# stereo_mix_back_digital.net
KiCad netlist of a schematic drawn in EAGLE
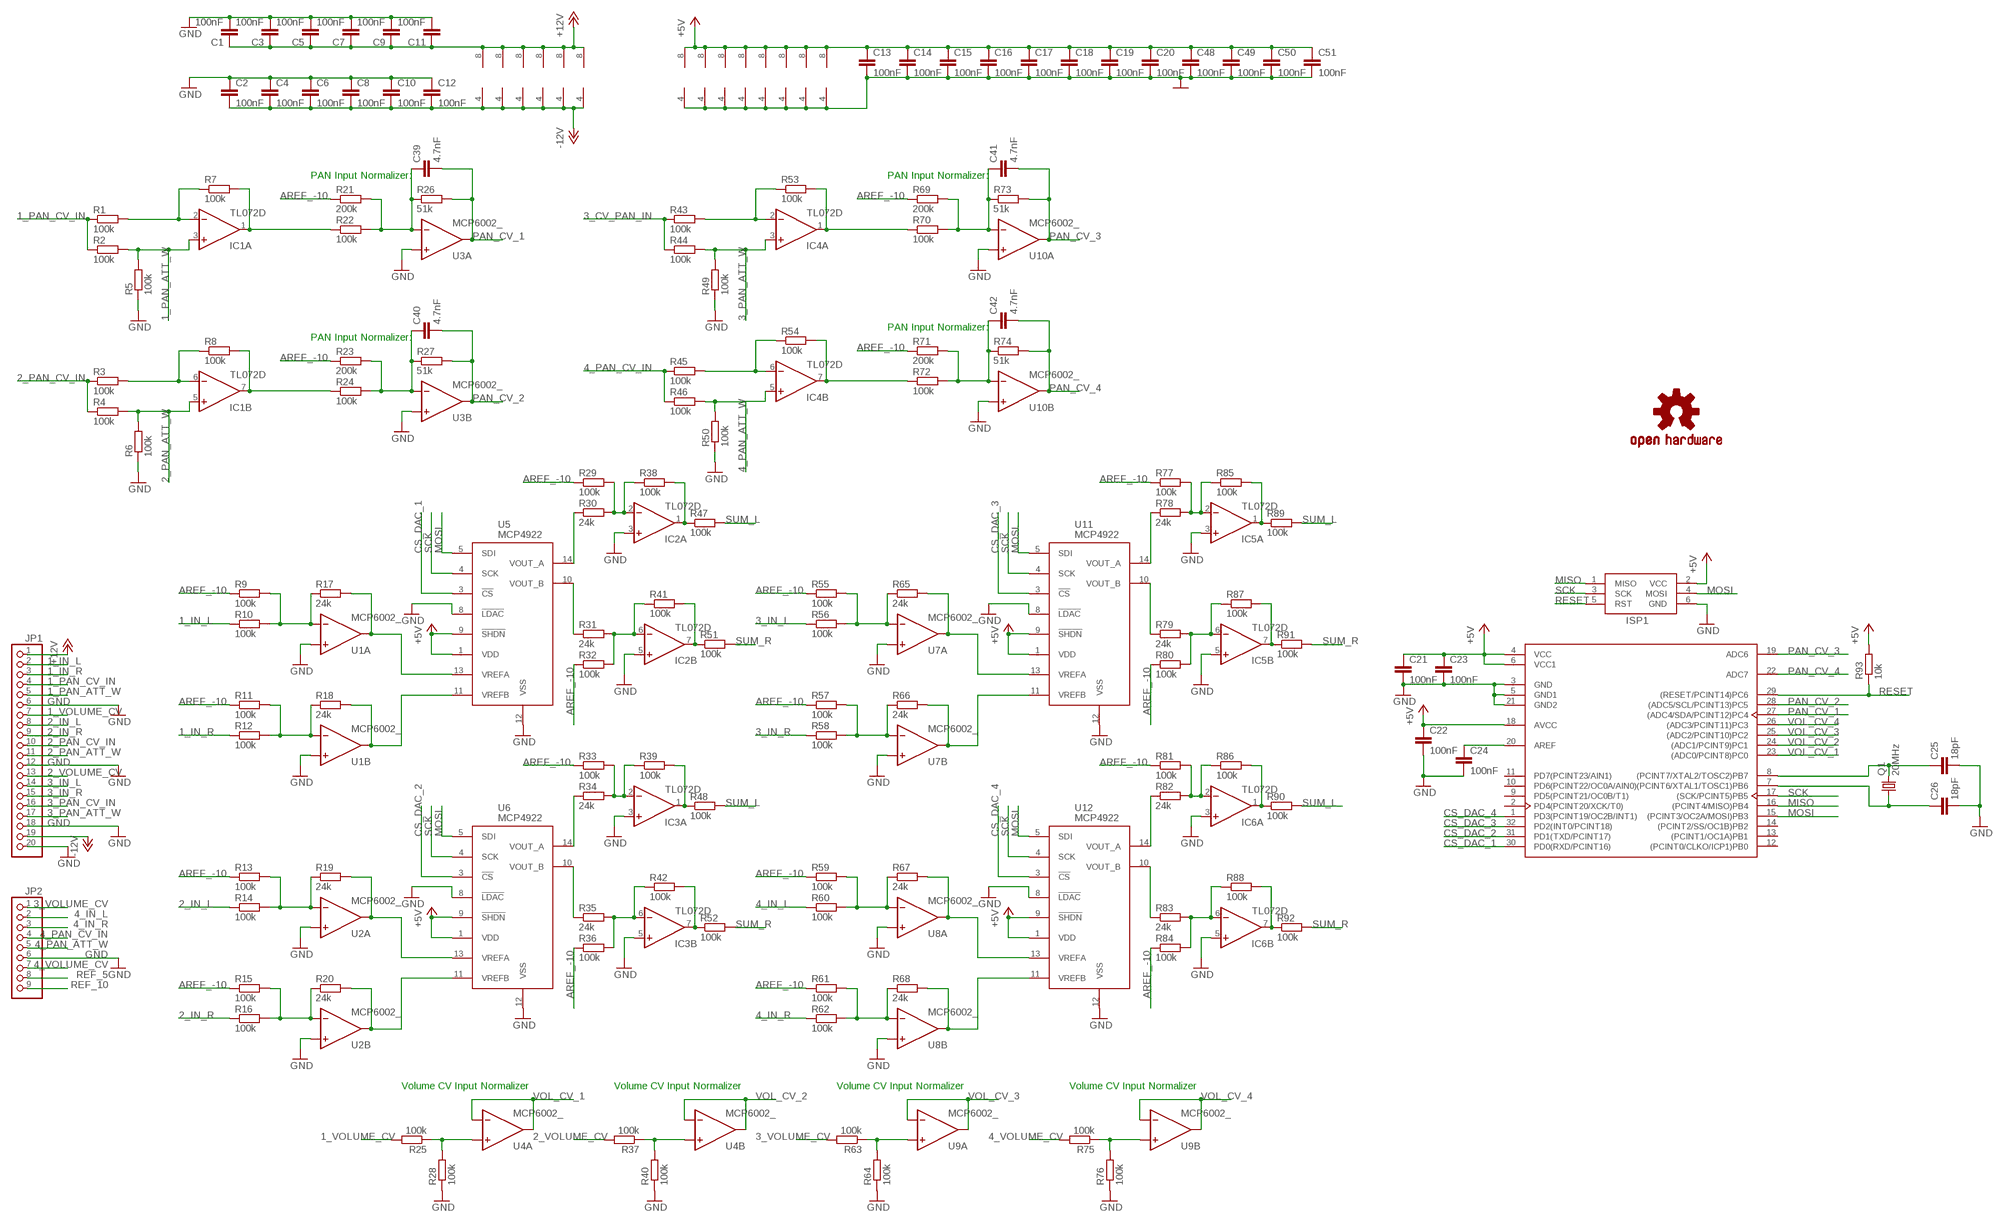
[diagram p0: schematic, sheet 1]
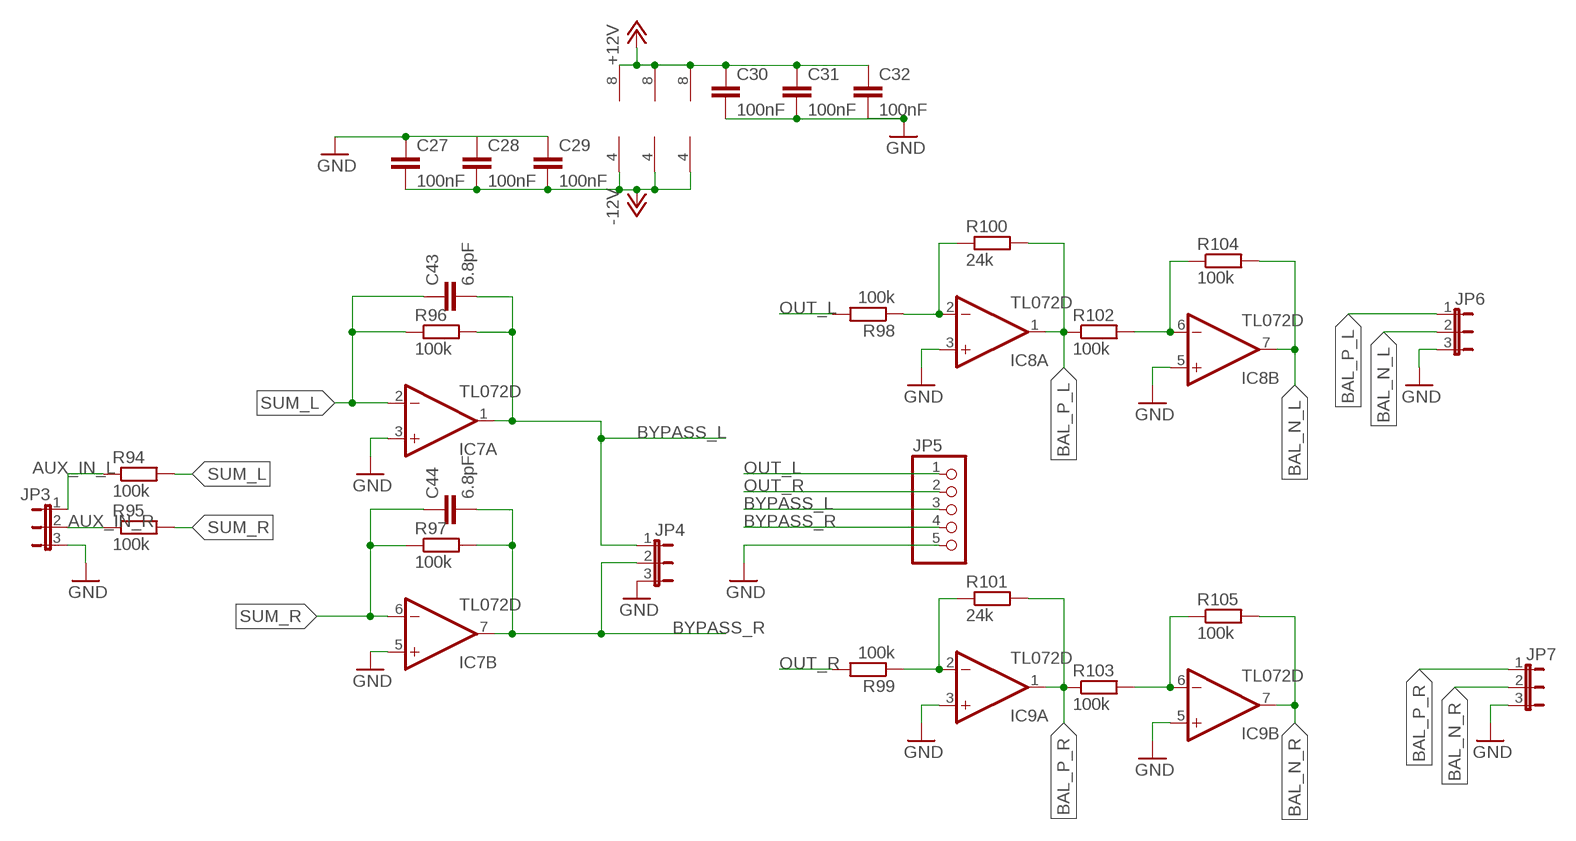
[diagram p1: schematic, sheet 2]
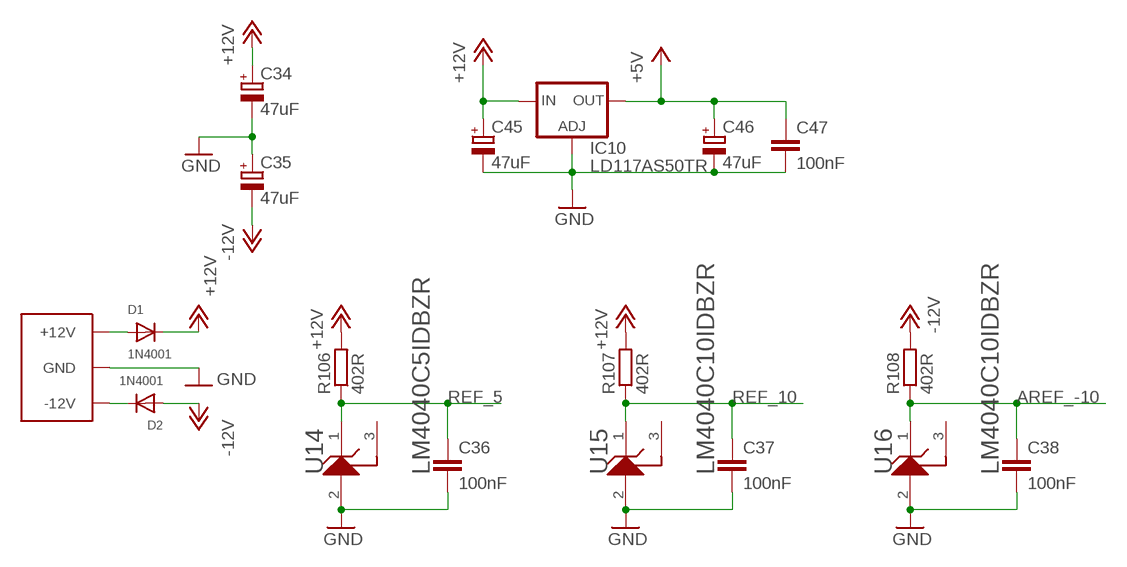
[diagram p2: schematic, sheet 3]

(export (version "E")
  (design (tool "Eeschema 10.0.6"))
  (components
    (comp (ref "C27")
      (value "100nF")
      (footprint "eagle-import:C0402")
      (libsource (lib "eagle-import") (part "resistor_348_C-EUC0402"))
    )
    (comp (ref "C28")
      (value "100nF")
      (footprint "eagle-import:C0402")
      (libsource (lib "eagle-import") (part "resistor_348_C-EUC0402"))
    )
    (comp (ref "C29")
      (value "100nF")
      (footprint "eagle-import:C0402")
      (libsource (lib "eagle-import") (part "resistor_348_C-EUC0402"))
    )
    (comp (ref "C30")
      (value "100nF")
      (footprint "eagle-import:C0402")
      (libsource (lib "eagle-import") (part "resistor_348_C-EUC0402"))
    )
    (comp (ref "C31")
      (value "100nF")
      (footprint "eagle-import:C0402")
      (libsource (lib "eagle-import") (part "resistor_348_C-EUC0402"))
    )
    (comp (ref "C32")
      (value "100nF")
      (footprint "eagle-import:C0402")
      (libsource (lib "eagle-import") (part "resistor_348_C-EUC0402"))
    )
    (comp (ref "C43")
      (value "6.8pF")
      (footprint "eagle-import:C0402")
      (libsource (lib "eagle-import") (part "resistor_348_C-EUC0402"))
    )
    (comp (ref "C44")
      (value "6.8pF")
      (footprint "eagle-import:C0402")
      (libsource (lib "eagle-import") (part "resistor_348_C-EUC0402"))
    )
    (comp (ref "IC7")
      (value "TL072D")
      (footprint "eagle-import:SO08")
      (libsource (lib "eagle-import") (part "TL072D"))
    )
    (comp (ref "IC8")
      (value "TL072D")
      (footprint "eagle-import:SO08")
      (libsource (lib "eagle-import") (part "TL072D"))
    )
    (comp (ref "IC9")
      (value "TL072D")
      (footprint "eagle-import:SO08")
      (libsource (lib "eagle-import") (part "TL072D"))
    )
    (comp (ref "JP3")
      (value "JP2E")
      (footprint "eagle-import:JP2")
      (libsource (lib "eagle-import") (part "JP2E"))
    )
    (comp (ref "JP4")
      (value "JP2E")
      (footprint "eagle-import:JP2")
      (libsource (lib "eagle-import") (part "JP2E"))
    )
    (comp (ref "JP5")
      (value "PINHD-1X5")
      (footprint "eagle-import:1X05")
      (libsource (lib "eagle-import") (part "PINHD-1X5"))
    )
    (comp (ref "JP6")
      (value "JP2E")
      (footprint "eagle-import:JP2")
      (libsource (lib "eagle-import") (part "JP2E"))
    )
    (comp (ref "JP7")
      (value "JP2E")
      (footprint "eagle-import:JP2")
      (libsource (lib "eagle-import") (part "JP2E"))
    )
    (comp (ref "R94")
      (value "100k")
      (footprint "eagle-import:R0402")
      (libsource (lib "eagle-import") (part "R-EU_R0402"))
    )
    (comp (ref "R95")
      (value "100k")
      (footprint "eagle-import:R0402")
      (libsource (lib "eagle-import") (part "R-EU_R0402"))
    )
    (comp (ref "R96")
      (value "100k")
      (footprint "eagle-import:R0402")
      (libsource (lib "eagle-import") (part "R-EU_R0402"))
    )
    (comp (ref "R97")
      (value "100k")
      (footprint "eagle-import:R0402")
      (libsource (lib "eagle-import") (part "R-EU_R0402"))
    )
    (comp (ref "R98")
      (value "100k")
      (footprint "eagle-import:R0402")
      (libsource (lib "eagle-import") (part "R-EU_R0402"))
    )
    (comp (ref "R99")
      (value "100k")
      (footprint "eagle-import:R0402")
      (libsource (lib "eagle-import") (part "R-EU_R0402"))
    )
    (comp (ref "R100")
      (value "24k")
      (footprint "eagle-import:R0402")
      (libsource (lib "eagle-import") (part "R-EU_R0402"))
    )
    (comp (ref "R101")
      (value "24k")
      (footprint "eagle-import:R0402")
      (libsource (lib "eagle-import") (part "R-EU_R0402"))
    )
    (comp (ref "R102")
      (value "100k")
      (footprint "eagle-import:R0402")
      (libsource (lib "eagle-import") (part "R-EU_R0402"))
    )
    (comp (ref "R103")
      (value "100k")
      (footprint "eagle-import:R0402")
      (libsource (lib "eagle-import") (part "R-EU_R0402"))
    )
    (comp (ref "R104")
      (value "100k")
      (footprint "eagle-import:R0402")
      (libsource (lib "eagle-import") (part "R-EU_R0402"))
    )
    (comp (ref "R105")
      (value "100k")
      (footprint "eagle-import:R0402")
      (libsource (lib "eagle-import") (part "R-EU_R0402"))
    )
    (comp (ref "C1")
      (value "100nF")
      (footprint "eagle-import:C0402")
      (libsource (lib "eagle-import") (part "resistor_348_C-EUC0402"))
    )
    (comp (ref "C2")
      (value "100nF")
      (footprint "eagle-import:C0402")
      (libsource (lib "eagle-import") (part "resistor_348_C-EUC0402"))
    )
    (comp (ref "C3")
      (value "100nF")
      (footprint "eagle-import:C0402")
      (libsource (lib "eagle-import") (part "resistor_348_C-EUC0402"))
    )
    (comp (ref "C4")
      (value "100nF")
      (footprint "eagle-import:C0402")
      (libsource (lib "eagle-import") (part "resistor_348_C-EUC0402"))
    )
    (comp (ref "C5")
      (value "100nF")
      (footprint "eagle-import:C0402")
      (libsource (lib "eagle-import") (part "resistor_348_C-EUC0402"))
    )
    (comp (ref "C6")
      (value "100nF")
      (footprint "eagle-import:C0402")
      (libsource (lib "eagle-import") (part "resistor_348_C-EUC0402"))
    )
    (comp (ref "C7")
      (value "100nF")
      (footprint "eagle-import:C0402")
      (libsource (lib "eagle-import") (part "resistor_348_C-EUC0402"))
    )
    (comp (ref "C8")
      (value "100nF")
      (footprint "eagle-import:C0402")
      (libsource (lib "eagle-import") (part "resistor_348_C-EUC0402"))
    )
    (comp (ref "C9")
      (value "100nF")
      (footprint "eagle-import:C0402")
      (libsource (lib "eagle-import") (part "resistor_348_C-EUC0402"))
    )
    (comp (ref "C10")
      (value "100nF")
      (footprint "eagle-import:C0402")
      (libsource (lib "eagle-import") (part "resistor_348_C-EUC0402"))
    )
    (comp (ref "C11")
      (value "100nF")
      (footprint "eagle-import:C0402")
      (libsource (lib "eagle-import") (part "resistor_348_C-EUC0402"))
    )
    (comp (ref "C12")
      (value "100nF")
      (footprint "eagle-import:C0402")
      (libsource (lib "eagle-import") (part "resistor_348_C-EUC0402"))
    )
    (comp (ref "C13")
      (value "100nF")
      (footprint "eagle-import:C0402")
      (libsource (lib "eagle-import") (part "resistor_348_C-EUC0402"))
    )
    (comp (ref "C14")
      (value "100nF")
      (footprint "eagle-import:C0402")
      (libsource (lib "eagle-import") (part "resistor_348_C-EUC0402"))
    )
    (comp (ref "C15")
      (value "100nF")
      (footprint "eagle-import:C0402")
      (libsource (lib "eagle-import") (part "resistor_348_C-EUC0402"))
    )
    (comp (ref "C16")
      (value "100nF")
      (footprint "eagle-import:C0402")
      (libsource (lib "eagle-import") (part "resistor_348_C-EUC0402"))
    )
    (comp (ref "C17")
      (value "100nF")
      (footprint "eagle-import:C0402")
      (libsource (lib "eagle-import") (part "resistor_348_C-EUC0402"))
    )
    (comp (ref "C18")
      (value "100nF")
      (footprint "eagle-import:C0402")
      (libsource (lib "eagle-import") (part "resistor_348_C-EUC0402"))
    )
    (comp (ref "C19")
      (value "100nF")
      (footprint "eagle-import:C0402")
      (libsource (lib "eagle-import") (part "resistor_348_C-EUC0402"))
    )
    (comp (ref "C20")
      (value "100nF")
      (footprint "eagle-import:C0402")
      (libsource (lib "eagle-import") (part "resistor_348_C-EUC0402"))
    )
    (comp (ref "C21")
      (value "100nF")
      (footprint "eagle-import:C0402")
      (libsource (lib "eagle-import") (part "resistor_348_C-EUC0402"))
    )
    (comp (ref "C22")
      (value "100nF")
      (footprint "eagle-import:C0402")
      (libsource (lib "eagle-import") (part "resistor_348_C-EUC0402"))
    )
    (comp (ref "C23")
      (value "100nF")
      (footprint "eagle-import:C0402")
      (libsource (lib "eagle-import") (part "resistor_348_C-EUC0402"))
    )
    (comp (ref "C24")
      (value "100nF")
      (footprint "eagle-import:C0402")
      (libsource (lib "eagle-import") (part "resistor_348_C-EUC0402"))
    )
    (comp (ref "C25")
      (value "18pF")
      (footprint "eagle-import:C0402")
      (libsource (lib "eagle-import") (part "resistor_348_C-EUC0402"))
    )
    (comp (ref "C26")
      (value "18pF")
      (footprint "eagle-import:C0402")
      (libsource (lib "eagle-import") (part "resistor_348_C-EUC0402"))
    )
    (comp (ref "C39")
      (value "4.7nF")
      (footprint "eagle-import:C0402")
      (libsource (lib "eagle-import") (part "resistor_348_C-EUC0402"))
    )
    (comp (ref "C40")
      (value "4.7nF")
      (footprint "eagle-import:C0402")
      (libsource (lib "eagle-import") (part "resistor_348_C-EUC0402"))
    )
    (comp (ref "C41")
      (value "4.7nF")
      (footprint "eagle-import:C0402")
      (libsource (lib "eagle-import") (part "resistor_348_C-EUC0402"))
    )
    (comp (ref "C42")
      (value "4.7nF")
      (footprint "eagle-import:C0402")
      (libsource (lib "eagle-import") (part "resistor_348_C-EUC0402"))
    )
    (comp (ref "C48")
      (value "100nF")
      (footprint "eagle-import:C0402")
      (libsource (lib "eagle-import") (part "resistor_348_C-EUC0402"))
    )
    (comp (ref "C49")
      (value "100nF")
      (footprint "eagle-import:C0402")
      (libsource (lib "eagle-import") (part "resistor_348_C-EUC0402"))
    )
    (comp (ref "C50")
      (value "100nF")
      (footprint "eagle-import:C0402")
      (libsource (lib "eagle-import") (part "resistor_348_C-EUC0402"))
    )
    (comp (ref "C51")
      (value "100nF")
      (footprint "eagle-import:C0402")
      (libsource (lib "eagle-import") (part "resistor_348_C-EUC0402"))
    )
    (comp (ref "IC1")
      (value "TL072D")
      (footprint "eagle-import:SO08")
      (libsource (lib "eagle-import") (part "TL072D"))
    )
    (comp (ref "IC2")
      (value "TL072D")
      (footprint "eagle-import:SO08")
      (libsource (lib "eagle-import") (part "TL072D"))
    )
    (comp (ref "IC3")
      (value "TL072D")
      (footprint "eagle-import:SO08")
      (libsource (lib "eagle-import") (part "TL072D"))
    )
    (comp (ref "IC4")
      (value "TL072D")
      (footprint "eagle-import:SO08")
      (libsource (lib "eagle-import") (part "TL072D"))
    )
    (comp (ref "IC5")
      (value "TL072D")
      (footprint "eagle-import:SO08")
      (libsource (lib "eagle-import") (part "TL072D"))
    )
    (comp (ref "IC6")
      (value "TL072D")
      (footprint "eagle-import:SO08")
      (libsource (lib "eagle-import") (part "TL072D"))
    )
    (comp (ref "ISP1")
      (value "AVRISP-6")
      (footprint "eagle-import:AVRISP")
      (libsource (lib "eagle-import") (part "AVRISP-6"))
    )
    (comp (ref "JP1")
      (value "PINHD-1X20")
      (footprint "eagle-import:1X20")
      (libsource (lib "eagle-import") (part "PINHD-1X20"))
    )
    (comp (ref "JP2")
      (value "PINHD-1X9")
      (footprint "eagle-import:1X09")
      (libsource (lib "eagle-import") (part "PINHD-1X9"))
    )
    (comp (ref "LOGO1")
      (value "OSHW-LOGOS")
      (footprint "eagle-import:OSHW-LOGO-S")
      (libsource (lib "eagle-import") (part "OSHW-LOGOS"))
    )
    (comp (ref "Q1")
      (value "20MHz")
      (footprint "eagle-import:HC49UP")
      (libsource (lib "eagle-import") (part "CRYSTALHC49UP"))
    )
    (comp (ref "R1")
      (value "100k")
      (footprint "eagle-import:R0402")
      (libsource (lib "eagle-import") (part "R-EU_R0402"))
    )
    (comp (ref "R2")
      (value "100k")
      (footprint "eagle-import:R0402")
      (libsource (lib "eagle-import") (part "R-EU_R0402"))
    )
    (comp (ref "R3")
      (value "100k")
      (footprint "eagle-import:R0402")
      (libsource (lib "eagle-import") (part "R-EU_R0402"))
    )
    (comp (ref "R4")
      (value "100k")
      (footprint "eagle-import:R0402")
      (libsource (lib "eagle-import") (part "R-EU_R0402"))
    )
    (comp (ref "R5")
      (value "100k")
      (footprint "eagle-import:R0402")
      (libsource (lib "eagle-import") (part "R-EU_R0402"))
    )
    (comp (ref "R6")
      (value "100k")
      (footprint "eagle-import:R0402")
      (libsource (lib "eagle-import") (part "R-EU_R0402"))
    )
    (comp (ref "R7")
      (value "100k")
      (footprint "eagle-import:R0402")
      (libsource (lib "eagle-import") (part "R-EU_R0402"))
    )
    (comp (ref "R8")
      (value "100k")
      (footprint "eagle-import:R0402")
      (libsource (lib "eagle-import") (part "R-EU_R0402"))
    )
    (comp (ref "R9")
      (value "100k")
      (footprint "eagle-import:R0402")
      (libsource (lib "eagle-import") (part "R-EU_R0402"))
    )
    (comp (ref "R10")
      (value "100k")
      (footprint "eagle-import:R0402")
      (libsource (lib "eagle-import") (part "R-EU_R0402"))
    )
    (comp (ref "R11")
      (value "100k")
      (footprint "eagle-import:R0402")
      (libsource (lib "eagle-import") (part "R-EU_R0402"))
    )
    (comp (ref "R12")
      (value "100k")
      (footprint "eagle-import:R0402")
      (libsource (lib "eagle-import") (part "R-EU_R0402"))
    )
    (comp (ref "R13")
      (value "100k")
      (footprint "eagle-import:R0402")
      (libsource (lib "eagle-import") (part "R-EU_R0402"))
    )
    (comp (ref "R14")
      (value "100k")
      (footprint "eagle-import:R0402")
      (libsource (lib "eagle-import") (part "R-EU_R0402"))
    )
    (comp (ref "R15")
      (value "100k")
      (footprint "eagle-import:R0402")
      (libsource (lib "eagle-import") (part "R-EU_R0402"))
    )
    (comp (ref "R16")
      (value "100k")
      (footprint "eagle-import:R0402")
      (libsource (lib "eagle-import") (part "R-EU_R0402"))
    )
    (comp (ref "R17")
      (value "24k")
      (footprint "eagle-import:R0402")
      (libsource (lib "eagle-import") (part "R-EU_R0402"))
    )
    (comp (ref "R18")
      (value "24k")
      (footprint "eagle-import:R0402")
      (libsource (lib "eagle-import") (part "R-EU_R0402"))
    )
    (comp (ref "R19")
      (value "24k")
      (footprint "eagle-import:R0402")
      (libsource (lib "eagle-import") (part "R-EU_R0402"))
    )
    (comp (ref "R20")
      (value "24k")
      (footprint "eagle-import:R0402")
      (libsource (lib "eagle-import") (part "R-EU_R0402"))
    )
    (comp (ref "R21")
      (value "200k")
      (footprint "eagle-import:R0402")
      (libsource (lib "eagle-import") (part "R-EU_R0402"))
    )
    (comp (ref "R22")
      (value "100k")
      (footprint "eagle-import:R0402")
      (libsource (lib "eagle-import") (part "R-EU_R0402"))
    )
    (comp (ref "R23")
      (value "200k")
      (footprint "eagle-import:R0402")
      (libsource (lib "eagle-import") (part "R-EU_R0402"))
    )
    (comp (ref "R24")
      (value "100k")
      (footprint "eagle-import:R0402")
      (libsource (lib "eagle-import") (part "R-EU_R0402"))
    )
    (comp (ref "R25")
      (value "100k")
      (footprint "eagle-import:R0402")
      (libsource (lib "eagle-import") (part "R-EU_R0402"))
    )
    (comp (ref "R26")
      (value "51k")
      (footprint "eagle-import:R0402")
      (libsource (lib "eagle-import") (part "R-EU_R0402"))
    )
    (comp (ref "R27")
      (value "51k")
      (footprint "eagle-import:R0402")
      (libsource (lib "eagle-import") (part "R-EU_R0402"))
    )
    (comp (ref "R28")
      (value "100k")
      (footprint "eagle-import:R0402")
      (libsource (lib "eagle-import") (part "R-EU_R0402"))
    )
    (comp (ref "R29")
      (value "100k")
      (footprint "eagle-import:R0402")
      (libsource (lib "eagle-import") (part "R-EU_R0402"))
    )
    (comp (ref "R30")
      (value "24k")
      (footprint "eagle-import:R0402")
      (libsource (lib "eagle-import") (part "R-EU_R0402"))
    )
    (comp (ref "R31")
      (value "24k")
      (footprint "eagle-import:R0402")
      (libsource (lib "eagle-import") (part "R-EU_R0402"))
    )
    (comp (ref "R32")
      (value "100k")
      (footprint "eagle-import:R0402")
      (libsource (lib "eagle-import") (part "R-EU_R0402"))
    )
    (comp (ref "R33")
      (value "100k")
      (footprint "eagle-import:R0402")
      (libsource (lib "eagle-import") (part "R-EU_R0402"))
    )
    (comp (ref "R34")
      (value "24k")
      (footprint "eagle-import:R0402")
      (libsource (lib "eagle-import") (part "R-EU_R0402"))
    )
    (comp (ref "R35")
      (value "24k")
      (footprint "eagle-import:R0402")
      (libsource (lib "eagle-import") (part "R-EU_R0402"))
    )
    (comp (ref "R36")
      (value "100k")
      (footprint "eagle-import:R0402")
      (libsource (lib "eagle-import") (part "R-EU_R0402"))
    )
    (comp (ref "R37")
      (value "100k")
      (footprint "eagle-import:R0402")
      (libsource (lib "eagle-import") (part "R-EU_R0402"))
    )
    (comp (ref "R38")
      (value "100k")
      (footprint "eagle-import:R0402")
      (libsource (lib "eagle-import") (part "R-EU_R0402"))
    )
    (comp (ref "R39")
      (value "100k")
      (footprint "eagle-import:R0402")
      (libsource (lib "eagle-import") (part "R-EU_R0402"))
    )
    (comp (ref "R40")
      (value "100k")
      (footprint "eagle-import:R0402")
      (libsource (lib "eagle-import") (part "R-EU_R0402"))
    )
    (comp (ref "R41")
      (value "100k")
      (footprint "eagle-import:R0402")
      (libsource (lib "eagle-import") (part "R-EU_R0402"))
    )
    (comp (ref "R42")
      (value "100k")
      (footprint "eagle-import:R0402")
      (libsource (lib "eagle-import") (part "R-EU_R0402"))
    )
    (comp (ref "R43")
      (value "100k")
      (footprint "eagle-import:R0402")
      (libsource (lib "eagle-import") (part "R-EU_R0402"))
    )
    (comp (ref "R44")
      (value "100k")
      (footprint "eagle-import:R0402")
      (libsource (lib "eagle-import") (part "R-EU_R0402"))
    )
    (comp (ref "R45")
      (value "100k")
      (footprint "eagle-import:R0402")
      (libsource (lib "eagle-import") (part "R-EU_R0402"))
    )
    (comp (ref "R46")
      (value "100k")
      (footprint "eagle-import:R0402")
      (libsource (lib "eagle-import") (part "R-EU_R0402"))
    )
    (comp (ref "R47")
      (value "100k")
      (footprint "eagle-import:R0402")
      (libsource (lib "eagle-import") (part "R-EU_R0402"))
    )
    (comp (ref "R48")
      (value "100k")
      (footprint "eagle-import:R0402")
      (libsource (lib "eagle-import") (part "R-EU_R0402"))
    )
    (comp (ref "R49")
      (value "100k")
      (footprint "eagle-import:R0402")
      (libsource (lib "eagle-import") (part "R-EU_R0402"))
    )
    (comp (ref "R50")
      (value "100k")
      (footprint "eagle-import:R0402")
      (libsource (lib "eagle-import") (part "R-EU_R0402"))
    )
    (comp (ref "R51")
      (value "100k")
      (footprint "eagle-import:R0402")
      (libsource (lib "eagle-import") (part "R-EU_R0402"))
    )
    (comp (ref "R52")
      (value "100k")
      (footprint "eagle-import:R0402")
      (libsource (lib "eagle-import") (part "R-EU_R0402"))
    )
    (comp (ref "R53")
      (value "100k")
      (footprint "eagle-import:R0402")
      (libsource (lib "eagle-import") (part "R-EU_R0402"))
    )
    (comp (ref "R54")
      (value "100k")
      (footprint "eagle-import:R0402")
      (libsource (lib "eagle-import") (part "R-EU_R0402"))
    )
    (comp (ref "R55")
      (value "100k")
      (footprint "eagle-import:R0402")
      (libsource (lib "eagle-import") (part "R-EU_R0402"))
    )
    (comp (ref "R56")
      (value "100k")
      (footprint "eagle-import:R0402")
      (libsource (lib "eagle-import") (part "R-EU_R0402"))
    )
    (comp (ref "R57")
      (value "100k")
      (footprint "eagle-import:R0402")
      (libsource (lib "eagle-import") (part "R-EU_R0402"))
    )
    (comp (ref "R58")
      (value "100k")
      (footprint "eagle-import:R0402")
      (libsource (lib "eagle-import") (part "R-EU_R0402"))
    )
    (comp (ref "R59")
      (value "100k")
      (footprint "eagle-import:R0402")
      (libsource (lib "eagle-import") (part "R-EU_R0402"))
    )
    (comp (ref "R60")
      (value "100k")
      (footprint "eagle-import:R0402")
      (libsource (lib "eagle-import") (part "R-EU_R0402"))
    )
    (comp (ref "R61")
      (value "100k")
      (footprint "eagle-import:R0402")
      (libsource (lib "eagle-import") (part "R-EU_R0402"))
    )
    (comp (ref "R62")
      (value "100k")
      (footprint "eagle-import:R0402")
      (libsource (lib "eagle-import") (part "R-EU_R0402"))
    )
    (comp (ref "R63")
      (value "100k")
      (footprint "eagle-import:R0402")
      (libsource (lib "eagle-import") (part "R-EU_R0402"))
    )
    (comp (ref "R64")
      (value "100k")
      (footprint "eagle-import:R0402")
      (libsource (lib "eagle-import") (part "R-EU_R0402"))
    )
    (comp (ref "R65")
      (value "24k")
      (footprint "eagle-import:R0402")
      (libsource (lib "eagle-import") (part "R-EU_R0402"))
    )
    (comp (ref "R66")
      (value "24k")
      (footprint "eagle-import:R0402")
      (libsource (lib "eagle-import") (part "R-EU_R0402"))
    )
    (comp (ref "R67")
      (value "24k")
      (footprint "eagle-import:R0402")
      (libsource (lib "eagle-import") (part "R-EU_R0402"))
    )
    (comp (ref "R68")
      (value "24k")
      (footprint "eagle-import:R0402")
      (libsource (lib "eagle-import") (part "R-EU_R0402"))
    )
    (comp (ref "R69")
      (value "200k")
      (footprint "eagle-import:R0402")
      (libsource (lib "eagle-import") (part "R-EU_R0402"))
    )
    (comp (ref "R70")
      (value "100k")
      (footprint "eagle-import:R0402")
      (libsource (lib "eagle-import") (part "R-EU_R0402"))
    )
    (comp (ref "R71")
      (value "200k")
      (footprint "eagle-import:R0402")
      (libsource (lib "eagle-import") (part "R-EU_R0402"))
    )
    (comp (ref "R72")
      (value "100k")
      (footprint "eagle-import:R0402")
      (libsource (lib "eagle-import") (part "R-EU_R0402"))
    )
    (comp (ref "R73")
      (value "51k")
      (footprint "eagle-import:R0402")
      (libsource (lib "eagle-import") (part "R-EU_R0402"))
    )
    (comp (ref "R74")
      (value "51k")
      (footprint "eagle-import:R0402")
      (libsource (lib "eagle-import") (part "R-EU_R0402"))
    )
    (comp (ref "R75")
      (value "100k")
      (footprint "eagle-import:R0402")
      (libsource (lib "eagle-import") (part "R-EU_R0402"))
    )
    (comp (ref "R76")
      (value "100k")
      (footprint "eagle-import:R0402")
      (libsource (lib "eagle-import") (part "R-EU_R0402"))
    )
    (comp (ref "R77")
      (value "100k")
      (footprint "eagle-import:R0402")
      (libsource (lib "eagle-import") (part "R-EU_R0402"))
    )
    (comp (ref "R78")
      (value "24k")
      (footprint "eagle-import:R0402")
      (libsource (lib "eagle-import") (part "R-EU_R0402"))
    )
    (comp (ref "R79")
      (value "24k")
      (footprint "eagle-import:R0402")
      (libsource (lib "eagle-import") (part "R-EU_R0402"))
    )
    (comp (ref "R80")
      (value "100k")
      (footprint "eagle-import:R0402")
      (libsource (lib "eagle-import") (part "R-EU_R0402"))
    )
    (comp (ref "R81")
      (value "100k")
      (footprint "eagle-import:R0402")
      (libsource (lib "eagle-import") (part "R-EU_R0402"))
    )
    (comp (ref "R82")
      (value "24k")
      (footprint "eagle-import:R0402")
      (libsource (lib "eagle-import") (part "R-EU_R0402"))
    )
    (comp (ref "R83")
      (value "24k")
      (footprint "eagle-import:R0402")
      (libsource (lib "eagle-import") (part "R-EU_R0402"))
    )
    (comp (ref "R84")
      (value "100k")
      (footprint "eagle-import:R0402")
      (libsource (lib "eagle-import") (part "R-EU_R0402"))
    )
    (comp (ref "R85")
      (value "100k")
      (footprint "eagle-import:R0402")
      (libsource (lib "eagle-import") (part "R-EU_R0402"))
    )
    (comp (ref "R86")
      (value "100k")
      (footprint "eagle-import:R0402")
      (libsource (lib "eagle-import") (part "R-EU_R0402"))
    )
    (comp (ref "R87")
      (value "100k")
      (footprint "eagle-import:R0402")
      (libsource (lib "eagle-import") (part "R-EU_R0402"))
    )
    (comp (ref "R88")
      (value "100k")
      (footprint "eagle-import:R0402")
      (libsource (lib "eagle-import") (part "R-EU_R0402"))
    )
    (comp (ref "R89")
      (value "100k")
      (footprint "eagle-import:R0402")
      (libsource (lib "eagle-import") (part "R-EU_R0402"))
    )
    (comp (ref "R90")
      (value "100k")
      (footprint "eagle-import:R0402")
      (libsource (lib "eagle-import") (part "R-EU_R0402"))
    )
    (comp (ref "R91")
      (value "100k")
      (footprint "eagle-import:R0402")
      (libsource (lib "eagle-import") (part "R-EU_R0402"))
    )
    (comp (ref "R92")
      (value "100k")
      (footprint "eagle-import:R0402")
      (libsource (lib "eagle-import") (part "R-EU_R0402"))
    )
    (comp (ref "R93")
      (value "10k")
      (footprint "eagle-import:R0402")
      (libsource (lib "eagle-import") (part "R-EU_R0402"))
    )
    (comp (ref "U1")
      (value "MCP6002_")
      (footprint "eagle-import:SO08")
      (libsource (lib "eagle-import") (part "MCP6002_"))
    )
    (comp (ref "U2")
      (value "MCP6002_")
      (footprint "eagle-import:SO08")
      (libsource (lib "eagle-import") (part "MCP6002_"))
    )
    (comp (ref "U3")
      (value "MCP6002_")
      (footprint "eagle-import:SO08")
      (libsource (lib "eagle-import") (part "MCP6002_"))
    )
    (comp (ref "U4")
      (value "MCP6002_")
      (footprint "eagle-import:SO08")
      (libsource (lib "eagle-import") (part "MCP6002_"))
    )
    (comp (ref "U5")
      (value "MCP4922")
      (footprint "eagle-import:SO-14")
      (libsource (lib "eagle-import") (part "MCP4922"))
    )
    (comp (ref "U6")
      (value "MCP4922")
      (footprint "eagle-import:SO-14")
      (libsource (lib "eagle-import") (part "MCP4922"))
    )
    (comp (ref "U7")
      (value "MCP6002_")
      (footprint "eagle-import:SO08")
      (libsource (lib "eagle-import") (part "MCP6002_"))
    )
    (comp (ref "U8")
      (value "MCP6002_")
      (footprint "eagle-import:SO08")
      (libsource (lib "eagle-import") (part "MCP6002_"))
    )
    (comp (ref "U9")
      (value "MCP6002_")
      (footprint "eagle-import:SO08")
      (libsource (lib "eagle-import") (part "MCP6002_"))
    )
    (comp (ref "U10")
      (value "MCP6002_")
      (footprint "eagle-import:SO08")
      (libsource (lib "eagle-import") (part "MCP6002_"))
    )
    (comp (ref "U11")
      (value "MCP4922")
      (footprint "eagle-import:SO-14")
      (libsource (lib "eagle-import") (part "MCP4922"))
    )
    (comp (ref "U12")
      (value "MCP4922")
      (footprint "eagle-import:SO-14")
      (libsource (lib "eagle-import") (part "MCP4922"))
    )
    (comp (ref "U13")
      (value "ATMEGA328P-AU")
      (footprint "eagle-import:TQFP-32")
      (fields
        (field (name "DIGIKEY_PART_NUMBER") "ATMEGA328P-AU-ND")
        (field (name "MANUFACTURER") "Microchip Technology")
        (field (name "CREATED_BY") "PCBLayout.com")
      )
      (libsource (lib "eagle-import") (part "ATMEGA328P-AU"))
    )
    (comp (ref "C33")
      (value "EURO_POWER_LOCKFAT-LOCK")
      (footprint "eagle-import:EURO_PWR_HEADER_LOCK")
      (libsource (lib "eagle-import") (part "EURO_POWER_LOCKFAT-LOCK"))
    )
    (comp (ref "C34")
      (value "47uF")
      (footprint "eagle-import:PANASONIC_C")
      (libsource (lib "eagle-import") (part "CPOL-EUC"))
    )
    (comp (ref "C35")
      (value "47uF")
      (footprint "eagle-import:PANASONIC_C")
      (libsource (lib "eagle-import") (part "CPOL-EUC"))
    )
    (comp (ref "C36")
      (value "100nF")
      (footprint "eagle-import:C0402")
      (libsource (lib "eagle-import") (part "resistor_348_C-EUC0402"))
    )
    (comp (ref "C37")
      (value "100nF")
      (footprint "eagle-import:C0402")
      (libsource (lib "eagle-import") (part "resistor_348_C-EUC0402"))
    )
    (comp (ref "C38")
      (value "100nF")
      (footprint "eagle-import:C0402")
      (libsource (lib "eagle-import") (part "resistor_348_C-EUC0402"))
    )
    (comp (ref "C45")
      (value "47uF")
      (footprint "eagle-import:PANASONIC_C")
      (libsource (lib "eagle-import") (part "CPOL-EUC"))
    )
    (comp (ref "C46")
      (value "47uF")
      (footprint "eagle-import:PANASONIC_C")
      (libsource (lib "eagle-import") (part "CPOL-EUC"))
    )
    (comp (ref "C47")
      (value "100nF")
      (footprint "eagle-import:C0402")
      (libsource (lib "eagle-import") (part "resistor_348_C-EUC0402"))
    )
    (comp (ref "D1")
      (value "1N4001")
      (footprint "eagle-import:SMADIODE")
      (libsource (lib "eagle-import") (part "DIODESMA"))
    )
    (comp (ref "D2")
      (value "1N4001")
      (footprint "eagle-import:SMADIODE")
      (libsource (lib "eagle-import") (part "DIODESMA"))
    )
    (comp (ref "IC10")
      (value "LD117AS50TR")
      (footprint "eagle-import:SOT223")
      (libsource (lib "eagle-import") (part "LD117A?S50TR"))
    )
    (comp (ref "R106")
      (value "402R")
      (footprint "eagle-import:R0402")
      (libsource (lib "eagle-import") (part "R-EU_R0402"))
    )
    (comp (ref "R107")
      (value "402R")
      (footprint "eagle-import:R0402")
      (libsource (lib "eagle-import") (part "R-EU_R0402"))
    )
    (comp (ref "R108")
      (value "402R")
      (footprint "eagle-import:R0402")
      (libsource (lib "eagle-import") (part "R-EU_R0402"))
    )
    (comp (ref "U14")
      (value "TEXAS_INSTRUMENTS_LM4040C5IDBZR")
      (footprint "eagle-import:TEXAS_INSTRUMENTS_LM4040C5IDBZR_0")
      (libsource (lib "eagle-import") (part "TEXAS_INSTRUMENTS_LM4040C5IDBZR"))
    )
    (comp (ref "U15")
      (value "TEXAS_INSTRUMENTS_LM4040C10IDBZR")
      (footprint "eagle-import:TEXAS_INSTRUMENTS_LM4040C5IDBZR_0")
      (libsource (lib "eagle-import") (part "TEXAS_INSTRUMENTS_LM4040C10IDBZR"))
    )
    (comp (ref "U16")
      (value "TEXAS_INSTRUMENTS_LM4040C10IDBZR")
      (footprint "eagle-import:TEXAS_INSTRUMENTS_LM4040C5IDBZR_0")
      (libsource (lib "eagle-import") (part "TEXAS_INSTRUMENTS_LM4040C10IDBZR"))
    )
  )
  (nets
    (net (code "1") (name "+5V") (class "Default")
      (node (ref "C13") (pin "1") (pinfunction "1_1") (pintype "passive"))
      (node (ref "C14") (pin "1") (pinfunction "1_1") (pintype "passive"))
      (node (ref "C15") (pin "1") (pinfunction "1_1") (pintype "passive"))
      (node (ref "C16") (pin "1") (pinfunction "1_1") (pintype "passive"))
      (node (ref "C17") (pin "1") (pinfunction "1_1") (pintype "passive"))
      (node (ref "C18") (pin "1") (pinfunction "1_1") (pintype "passive"))
      (node (ref "C19") (pin "1") (pinfunction "1_1") (pintype "passive"))
      (node (ref "C20") (pin "1") (pinfunction "1_1") (pintype "passive"))
      (node (ref "C21") (pin "1") (pinfunction "1_1") (pintype "passive"))
      (node (ref "C22") (pin "1") (pinfunction "1_1") (pintype "passive"))
      (node (ref "C23") (pin "1") (pinfunction "1_1") (pintype "passive"))
      (node (ref "C46") (pin "+") (pinfunction "+_+") (pintype "passive"))
      (node (ref "C47") (pin "1") (pinfunction "1_1") (pintype "passive"))
      (node (ref "C48") (pin "1") (pinfunction "1_1") (pintype "passive"))
      (node (ref "C49") (pin "1") (pinfunction "1_1") (pintype "passive"))
      (node (ref "C50") (pin "1") (pinfunction "1_1") (pintype "passive"))
      (node (ref "C51") (pin "1") (pinfunction "1_1") (pintype "passive"))
      (node (ref "IC10") (pin "4") (pinfunction "OUT_4") (pintype "passive"))
      (node (ref "ISP1") (pin "2") (pinfunction "VCC_2") (pintype "power_in"))
      (node (ref "R93") (pin "2") (pinfunction "2_2") (pintype "passive"))
      (node (ref "U1") (pin "8") (pinfunction "V+_8") (pintype "power_in"))
      (node (ref "U10") (pin "8") (pinfunction "V+_8") (pintype "power_in"))
      (node (ref "U11") (pin "1") (pinfunction "VDD_1") (pintype "bidirectional"))
      (node (ref "U11") (pin "9") (pinfunction "~{SHDN}_9") (pintype "bidirectional"))
      (node (ref "U12") (pin "1") (pinfunction "VDD_1") (pintype "bidirectional"))
      (node (ref "U12") (pin "9") (pinfunction "~{SHDN}_9") (pintype "bidirectional"))
      (node (ref "U13") (pin "18") (pinfunction "AVCC_18") (pintype "power_in"))
      (node (ref "U13") (pin "4") (pinfunction "VCC_4") (pintype "power_in"))
      (node (ref "U13") (pin "6") (pinfunction "VCC1_6") (pintype "power_in"))
      (node (ref "U2") (pin "8") (pinfunction "V+_8") (pintype "power_in"))
      (node (ref "U3") (pin "8") (pinfunction "V+_8") (pintype "power_in"))
      (node (ref "U4") (pin "8") (pinfunction "V+_8") (pintype "power_in"))
      (node (ref "U5") (pin "1") (pinfunction "VDD_1") (pintype "bidirectional"))
      (node (ref "U5") (pin "9") (pinfunction "~{SHDN}_9") (pintype "bidirectional"))
      (node (ref "U6") (pin "1") (pinfunction "VDD_1") (pintype "bidirectional"))
      (node (ref "U6") (pin "9") (pinfunction "~{SHDN}_9") (pintype "bidirectional"))
      (node (ref "U7") (pin "8") (pinfunction "V+_8") (pintype "power_in"))
      (node (ref "U8") (pin "8") (pinfunction "V+_8") (pintype "power_in"))
      (node (ref "U9") (pin "8") (pinfunction "V+_8") (pintype "power_in"))
    )
    (net (code "2") (name "+12V") (class "Default")
      (node (ref "C1") (pin "1") (pinfunction "1_1") (pintype "passive"))
      (node (ref "C11") (pin "1") (pinfunction "1_1") (pintype "passive"))
      (node (ref "C3") (pin "1") (pinfunction "1_1") (pintype "passive"))
      (node (ref "C30") (pin "1") (pinfunction "1_1") (pintype "passive"))
      (node (ref "C31") (pin "1") (pinfunction "1_1") (pintype "passive"))
      (node (ref "C32") (pin "1") (pinfunction "1_1") (pintype "passive"))
      (node (ref "C34") (pin "+") (pinfunction "+_+") (pintype "passive"))
      (node (ref "C45") (pin "+") (pinfunction "+_+") (pintype "passive"))
      (node (ref "C5") (pin "1") (pinfunction "1_1") (pintype "passive"))
      (node (ref "C7") (pin "1") (pinfunction "1_1") (pintype "passive"))
      (node (ref "C9") (pin "1") (pinfunction "1_1") (pintype "passive"))
      (node (ref "D1") (pin "C") (pinfunction "C_C") (pintype "passive"))
      (node (ref "IC1") (pin "8") (pinfunction "V+_8") (pintype "power_in"))
      (node (ref "IC10") (pin "3") (pinfunction "IN_3") (pintype "input"))
      (node (ref "IC2") (pin "8") (pinfunction "V+_8") (pintype "power_in"))
      (node (ref "IC3") (pin "8") (pinfunction "V+_8") (pintype "power_in"))
      (node (ref "IC4") (pin "8") (pinfunction "V+_8") (pintype "power_in"))
      (node (ref "IC5") (pin "8") (pinfunction "V+_8") (pintype "power_in"))
      (node (ref "IC6") (pin "8") (pinfunction "V+_8") (pintype "power_in"))
      (node (ref "IC7") (pin "8") (pinfunction "V+_8") (pintype "power_in"))
      (node (ref "IC8") (pin "8") (pinfunction "V+_8") (pintype "power_in"))
      (node (ref "IC9") (pin "8") (pinfunction "V+_8") (pintype "power_in"))
      (node (ref "JP1") (pin "1") (pinfunction "1_1") (pintype "passive"))
      (node (ref "R106") (pin "2") (pinfunction "2_2") (pintype "passive"))
      (node (ref "R107") (pin "2") (pinfunction "2_2") (pintype "passive"))
    )
    (net (code "3") (name "-12V") (class "Default")
      (node (ref "C10") (pin "2") (pinfunction "2_2") (pintype "passive"))
      (node (ref "C12") (pin "2") (pinfunction "2_2") (pintype "passive"))
      (node (ref "C2") (pin "2") (pinfunction "2_2") (pintype "passive"))
      (node (ref "C27") (pin "2") (pinfunction "2_2") (pintype "passive"))
      (node (ref "C28") (pin "2") (pinfunction "2_2") (pintype "passive"))
      (node (ref "C29") (pin "2") (pinfunction "2_2") (pintype "passive"))
      (node (ref "C35") (pin "-") (pinfunction "-_-") (pintype "passive"))
      (node (ref "C4") (pin "2") (pinfunction "2_2") (pintype "passive"))
      (node (ref "C6") (pin "2") (pinfunction "2_2") (pintype "passive"))
      (node (ref "C8") (pin "2") (pinfunction "2_2") (pintype "passive"))
      (node (ref "D2") (pin "A") (pinfunction "A_A") (pintype "passive"))
      (node (ref "IC1") (pin "4") (pinfunction "V-_4") (pintype "power_in"))
      (node (ref "IC2") (pin "4") (pinfunction "V-_4") (pintype "power_in"))
      (node (ref "IC3") (pin "4") (pinfunction "V-_4") (pintype "power_in"))
      (node (ref "IC4") (pin "4") (pinfunction "V-_4") (pintype "power_in"))
      (node (ref "IC5") (pin "4") (pinfunction "V-_4") (pintype "power_in"))
      (node (ref "IC6") (pin "4") (pinfunction "V-_4") (pintype "power_in"))
      (node (ref "IC7") (pin "4") (pinfunction "V-_4") (pintype "power_in"))
      (node (ref "IC8") (pin "4") (pinfunction "V-_4") (pintype "power_in"))
      (node (ref "IC9") (pin "4") (pinfunction "V-_4") (pintype "power_in"))
      (node (ref "JP1") (pin "19") (pinfunction "19_19") (pintype "passive"))
      (node (ref "R108") (pin "2") (pinfunction "2_2") (pintype "passive"))
    )
    (net (code "4") (name "1_IN_L") (class "Default")
      (node (ref "JP1") (pin "2") (pinfunction "2_2") (pintype "passive"))
      (node (ref "R10") (pin "1") (pinfunction "1_1") (pintype "passive"))
    )
    (net (code "5") (name "1_IN_R") (class "Default")
      (node (ref "JP1") (pin "3") (pinfunction "3_3") (pintype "passive"))
      (node (ref "R12") (pin "1") (pinfunction "1_1") (pintype "passive"))
    )
    (net (code "6") (name "1_PAN_ATT_W") (class "Default")
      (node (ref "IC1") (pin "3") (pinfunction "+IN_3") (pintype "input"))
      (node (ref "JP1") (pin "5") (pinfunction "5_5") (pintype "passive"))
      (node (ref "R2") (pin "2") (pinfunction "2_2") (pintype "passive"))
      (node (ref "R5") (pin "2") (pinfunction "2_2") (pintype "passive"))
    )
    (net (code "7") (name "1_PAN_CV_IN") (class "Default")
      (node (ref "JP1") (pin "4") (pinfunction "4_4") (pintype "passive"))
      (node (ref "R1") (pin "1") (pinfunction "1_1") (pintype "passive"))
      (node (ref "R2") (pin "1") (pinfunction "1_1") (pintype "passive"))
    )
    (net (code "8") (name "1_VOLUME_CV") (class "Default")
      (node (ref "JP1") (pin "7") (pinfunction "7_7") (pintype "passive"))
      (node (ref "R25") (pin "2") (pinfunction "2_2") (pintype "passive"))
    )
    (net (code "9") (name "2_IN_L") (class "Default")
      (node (ref "JP1") (pin "8") (pinfunction "8_8") (pintype "passive"))
      (node (ref "R14") (pin "1") (pinfunction "1_1") (pintype "passive"))
    )
    (net (code "10") (name "2_IN_R") (class "Default")
      (node (ref "JP1") (pin "9") (pinfunction "9_9") (pintype "passive"))
      (node (ref "R16") (pin "1") (pinfunction "1_1") (pintype "passive"))
    )
    (net (code "11") (name "2_PAN_ATT_W") (class "Default")
      (node (ref "IC1") (pin "5") (pinfunction "+IN_5") (pintype "input"))
      (node (ref "JP1") (pin "11") (pinfunction "11_11") (pintype "passive"))
      (node (ref "R4") (pin "2") (pinfunction "2_2") (pintype "passive"))
      (node (ref "R6") (pin "2") (pinfunction "2_2") (pintype "passive"))
    )
    (net (code "12") (name "2_PAN_CV_IN") (class "Default")
      (node (ref "JP1") (pin "10") (pinfunction "10_10") (pintype "passive"))
      (node (ref "R3") (pin "1") (pinfunction "1_1") (pintype "passive"))
      (node (ref "R4") (pin "1") (pinfunction "1_1") (pintype "passive"))
    )
    (net (code "13") (name "2_VOLUME_CV") (class "Default")
      (node (ref "JP1") (pin "13") (pinfunction "13_13") (pintype "passive"))
      (node (ref "R37") (pin "2") (pinfunction "2_2") (pintype "passive"))
    )
    (net (code "14") (name "3_CV_PAN_IN") (class "Default")
      (node (ref "R43") (pin "1") (pinfunction "1_1") (pintype "passive"))
      (node (ref "R44") (pin "1") (pinfunction "1_1") (pintype "passive"))
    )
    (net (code "15") (name "3_IN_L") (class "Default")
      (node (ref "JP1") (pin "14") (pinfunction "14_14") (pintype "passive"))
      (node (ref "R56") (pin "1") (pinfunction "1_1") (pintype "passive"))
    )
    (net (code "16") (name "3_IN_R") (class "Default")
      (node (ref "JP1") (pin "15") (pinfunction "15_15") (pintype "passive"))
      (node (ref "R58") (pin "1") (pinfunction "1_1") (pintype "passive"))
    )
    (net (code "17") (name "3_PAN_ATT_W") (class "Default")
      (node (ref "IC4") (pin "3") (pinfunction "+IN_3") (pintype "input"))
      (node (ref "JP1") (pin "17") (pinfunction "17_17") (pintype "passive"))
      (node (ref "R44") (pin "2") (pinfunction "2_2") (pintype "passive"))
      (node (ref "R49") (pin "2") (pinfunction "2_2") (pintype "passive"))
    )
    (net (code "18") (name "3_PAN_CV_IN") (class "Default")
      (node (ref "JP1") (pin "16") (pinfunction "16_16") (pintype "passive"))
    )
    (net (code "19") (name "3_VOLUME_CV") (class "Default")
      (node (ref "JP2") (pin "1") (pinfunction "1_1") (pintype "passive"))
      (node (ref "R63") (pin "2") (pinfunction "2_2") (pintype "passive"))
    )
    (net (code "20") (name "4_IN_L") (class "Default")
      (node (ref "JP2") (pin "2") (pinfunction "2_2") (pintype "passive"))
      (node (ref "R60") (pin "1") (pinfunction "1_1") (pintype "passive"))
    )
    (net (code "21") (name "4_IN_R") (class "Default")
      (node (ref "JP2") (pin "3") (pinfunction "3_3") (pintype "passive"))
      (node (ref "R62") (pin "1") (pinfunction "1_1") (pintype "passive"))
    )
    (net (code "22") (name "4_PAN_ATT_W") (class "Default")
      (node (ref "IC4") (pin "5") (pinfunction "+IN_5") (pintype "input"))
      (node (ref "JP2") (pin "5") (pinfunction "5_5") (pintype "passive"))
      (node (ref "R46") (pin "2") (pinfunction "2_2") (pintype "passive"))
      (node (ref "R50") (pin "2") (pinfunction "2_2") (pintype "passive"))
    )
    (net (code "23") (name "4_PAN_CV_IN") (class "Default")
      (node (ref "JP2") (pin "4") (pinfunction "4_4") (pintype "passive"))
      (node (ref "R45") (pin "1") (pinfunction "1_1") (pintype "passive"))
      (node (ref "R46") (pin "1") (pinfunction "1_1") (pintype "passive"))
    )
    (net (code "24") (name "4_VOLUME_CV") (class "Default")
      (node (ref "JP2") (pin "7") (pinfunction "7_7") (pintype "passive"))
      (node (ref "R75") (pin "2") (pinfunction "2_2") (pintype "passive"))
    )
    (net (code "25") (name "AREF_-10") (class "Default")
      (node (ref "C38") (pin "1") (pinfunction "1_1") (pintype "passive"))
      (node (ref "R108") (pin "1") (pinfunction "1_1") (pintype "passive"))
      (node (ref "R11") (pin "1") (pinfunction "1_1") (pintype "passive"))
      (node (ref "R13") (pin "1") (pinfunction "1_1") (pintype "passive"))
      (node (ref "R15") (pin "1") (pinfunction "1_1") (pintype "passive"))
      (node (ref "R21") (pin "1") (pinfunction "1_1") (pintype "passive"))
      (node (ref "R23") (pin "1") (pinfunction "1_1") (pintype "passive"))
      (node (ref "R29") (pin "1") (pinfunction "1_1") (pintype "passive"))
      (node (ref "R32") (pin "1") (pinfunction "1_1") (pintype "passive"))
      (node (ref "R33") (pin "1") (pinfunction "1_1") (pintype "passive"))
      (node (ref "R36") (pin "1") (pinfunction "1_1") (pintype "passive"))
      (node (ref "R55") (pin "1") (pinfunction "1_1") (pintype "passive"))
      (node (ref "R57") (pin "1") (pinfunction "1_1") (pintype "passive"))
      (node (ref "R59") (pin "1") (pinfunction "1_1") (pintype "passive"))
      (node (ref "R61") (pin "1") (pinfunction "1_1") (pintype "passive"))
      (node (ref "R69") (pin "1") (pinfunction "1_1") (pintype "passive"))
      (node (ref "R71") (pin "1") (pinfunction "1_1") (pintype "passive"))
      (node (ref "R77") (pin "1") (pinfunction "1_1") (pintype "passive"))
      (node (ref "R80") (pin "1") (pinfunction "1_1") (pintype "passive"))
      (node (ref "R81") (pin "1") (pinfunction "1_1") (pintype "passive"))
      (node (ref "R84") (pin "1") (pinfunction "1_1") (pintype "passive"))
      (node (ref "R9") (pin "1") (pinfunction "1_1") (pintype "passive"))
      (node (ref "U16") (pin "1") (pinfunction "CATHODE_1") (pintype "passive"))
    )
    (net (code "26") (name "AUX_IN_L") (class "Default")
      (node (ref "JP3") (pin "1") (pinfunction "1_1") (pintype "passive"))
      (node (ref "R94") (pin "1") (pinfunction "1_1") (pintype "passive"))
    )
    (net (code "27") (name "AUX_IN_R") (class "Default")
      (node (ref "JP3") (pin "2") (pinfunction "2_2") (pintype "passive"))
      (node (ref "R95") (pin "1") (pinfunction "1_1") (pintype "passive"))
    )
    (net (code "28") (name "BAL_N_L") (class "Default")
      (node (ref "IC8") (pin "7") (pinfunction "OUT_7") (pintype "output"))
      (node (ref "JP6") (pin "2") (pinfunction "2_2") (pintype "passive"))
      (node (ref "R104") (pin "2") (pinfunction "2_2") (pintype "passive"))
    )
    (net (code "29") (name "BAL_N_R") (class "Default")
      (node (ref "IC9") (pin "7") (pinfunction "OUT_7") (pintype "output"))
      (node (ref "JP7") (pin "2") (pinfunction "2_2") (pintype "passive"))
      (node (ref "R105") (pin "2") (pinfunction "2_2") (pintype "passive"))
    )
    (net (code "30") (name "BAL_P_L") (class "Default")
      (node (ref "IC8") (pin "1") (pinfunction "OUT_1") (pintype "output"))
      (node (ref "JP6") (pin "1") (pinfunction "1_1") (pintype "passive"))
      (node (ref "R100") (pin "2") (pinfunction "2_2") (pintype "passive"))
      (node (ref "R102") (pin "1") (pinfunction "1_1") (pintype "passive"))
    )
    (net (code "31") (name "BAL_P_R") (class "Default")
      (node (ref "IC9") (pin "1") (pinfunction "OUT_1") (pintype "output"))
      (node (ref "JP7") (pin "1") (pinfunction "1_1") (pintype "passive"))
      (node (ref "R101") (pin "2") (pinfunction "2_2") (pintype "passive"))
      (node (ref "R103") (pin "1") (pinfunction "1_1") (pintype "passive"))
    )
    (net (code "32") (name "BYPASS_L") (class "Default")
      (node (ref "C43") (pin "2") (pinfunction "2_2") (pintype "passive"))
      (node (ref "IC7") (pin "1") (pinfunction "OUT_1") (pintype "output"))
      (node (ref "JP4") (pin "1") (pinfunction "1_1") (pintype "passive"))
      (node (ref "JP5") (pin "3") (pinfunction "3_3") (pintype "passive"))
      (node (ref "R96") (pin "2") (pinfunction "2_2") (pintype "passive"))
    )
    (net (code "33") (name "BYPASS_R") (class "Default")
      (node (ref "C44") (pin "2") (pinfunction "2_2") (pintype "passive"))
      (node (ref "IC7") (pin "7") (pinfunction "OUT_7") (pintype "output"))
      (node (ref "JP4") (pin "2") (pinfunction "2_2") (pintype "passive"))
      (node (ref "JP5") (pin "4") (pinfunction "4_4") (pintype "passive"))
      (node (ref "R97") (pin "2") (pinfunction "2_2") (pintype "passive"))
    )
    (net (code "34") (name "CS_DAC_1") (class "Default")
      (node (ref "U13") (pin "30") (pinfunction "PD0(RXD/PCINT16)_30") (pintype "bidirectional"))
      (node (ref "U5") (pin "3") (pinfunction "~{CS}_3") (pintype "bidirectional"))
    )
    (net (code "35") (name "CS_DAC_2") (class "Default")
      (node (ref "U13") (pin "31") (pinfunction "PD1(TXD/PCINT17)_31") (pintype "bidirectional"))
      (node (ref "U6") (pin "3") (pinfunction "~{CS}_3") (pintype "bidirectional"))
    )
    (net (code "36") (name "CS_DAC_3") (class "Default")
      (node (ref "U11") (pin "3") (pinfunction "~{CS}_3") (pintype "bidirectional"))
      (node (ref "U13") (pin "32") (pinfunction "PD2(INT0/PCINT18)_32") (pintype "bidirectional"))
    )
    (net (code "37") (name "CS_DAC_4") (class "Default")
      (node (ref "U12") (pin "3") (pinfunction "~{CS}_3") (pintype "bidirectional"))
      (node (ref "U13") (pin "1") (pinfunction "PD3(PCINT19/OC2B/INT1)_1") (pintype "bidirectional"))
    )
    (net (code "38") (name "GND") (class "Default")
      (node (ref "C1") (pin "2") (pinfunction "2_2") (pintype "passive"))
      (node (ref "C10") (pin "1") (pinfunction "1_1") (pintype "passive"))
      (node (ref "C11") (pin "2") (pinfunction "2_2") (pintype "passive"))
      (node (ref "C12") (pin "1") (pinfunction "1_1") (pintype "passive"))
      (node (ref "C13") (pin "2") (pinfunction "2_2") (pintype "passive"))
      (node (ref "C14") (pin "2") (pinfunction "2_2") (pintype "passive"))
      (node (ref "C15") (pin "2") (pinfunction "2_2") (pintype "passive"))
      (node (ref "C16") (pin "2") (pinfunction "2_2") (pintype "passive"))
      (node (ref "C17") (pin "2") (pinfunction "2_2") (pintype "passive"))
      (node (ref "C18") (pin "2") (pinfunction "2_2") (pintype "passive"))
      (node (ref "C19") (pin "2") (pinfunction "2_2") (pintype "passive"))
      (node (ref "C2") (pin "1") (pinfunction "1_1") (pintype "passive"))
      (node (ref "C20") (pin "2") (pinfunction "2_2") (pintype "passive"))
      (node (ref "C21") (pin "2") (pinfunction "2_2") (pintype "passive"))
      (node (ref "C22") (pin "2") (pinfunction "2_2") (pintype "passive"))
      (node (ref "C23") (pin "2") (pinfunction "2_2") (pintype "passive"))
      (node (ref "C24") (pin "2") (pinfunction "2_2") (pintype "passive"))
      (node (ref "C25") (pin "2") (pinfunction "2_2") (pintype "passive"))
      (node (ref "C26") (pin "2") (pinfunction "2_2") (pintype "passive"))
      (node (ref "C27") (pin "1") (pinfunction "1_1") (pintype "passive"))
      (node (ref "C28") (pin "1") (pinfunction "1_1") (pintype "passive"))
      (node (ref "C29") (pin "1") (pinfunction "1_1") (pintype "passive"))
      (node (ref "C3") (pin "2") (pinfunction "2_2") (pintype "passive"))
      (node (ref "C30") (pin "2") (pinfunction "2_2") (pintype "passive"))
      (node (ref "C31") (pin "2") (pinfunction "2_2") (pintype "passive"))
      (node (ref "C32") (pin "2") (pinfunction "2_2") (pintype "passive"))
      (node (ref "C33") (pin "GND1") (pinfunction "GND_GND1") (pintype "bidirectional"))
      (node (ref "C33") (pin "GND2") (pinfunction "GND_GND2") (pintype "bidirectional"))
      (node (ref "C33") (pin "GND3") (pinfunction "GND_GND3") (pintype "bidirectional"))
      (node (ref "C33") (pin "GND4") (pinfunction "GND_GND4") (pintype "bidirectional"))
      (node (ref "C33") (pin "GND5") (pinfunction "GND_GND5") (pintype "bidirectional"))
      (node (ref "C33") (pin "GND6") (pinfunction "GND_GND6") (pintype "bidirectional"))
      (node (ref "C34") (pin "-") (pinfunction "-_-") (pintype "passive"))
      (node (ref "C35") (pin "+") (pinfunction "+_+") (pintype "passive"))
      (node (ref "C36") (pin "2") (pinfunction "2_2") (pintype "passive"))
      (node (ref "C37") (pin "2") (pinfunction "2_2") (pintype "passive"))
      (node (ref "C38") (pin "2") (pinfunction "2_2") (pintype "passive"))
      (node (ref "C4") (pin "1") (pinfunction "1_1") (pintype "passive"))
      (node (ref "C45") (pin "-") (pinfunction "-_-") (pintype "passive"))
      (node (ref "C46") (pin "-") (pinfunction "-_-") (pintype "passive"))
      (node (ref "C47") (pin "2") (pinfunction "2_2") (pintype "passive"))
      (node (ref "C48") (pin "2") (pinfunction "2_2") (pintype "passive"))
      (node (ref "C49") (pin "2") (pinfunction "2_2") (pintype "passive"))
      (node (ref "C5") (pin "2") (pinfunction "2_2") (pintype "passive"))
      (node (ref "C50") (pin "2") (pinfunction "2_2") (pintype "passive"))
      (node (ref "C51") (pin "2") (pinfunction "2_2") (pintype "passive"))
      (node (ref "C6") (pin "1") (pinfunction "1_1") (pintype "passive"))
      (node (ref "C7") (pin "2") (pinfunction "2_2") (pintype "passive"))
      (node (ref "C8") (pin "1") (pinfunction "1_1") (pintype "passive"))
      (node (ref "C9") (pin "2") (pinfunction "2_2") (pintype "passive"))
      (node (ref "IC10") (pin "1") (pinfunction "ADJ_1") (pintype "input"))
      (node (ref "IC2") (pin "3") (pinfunction "+IN_3") (pintype "input"))
      (node (ref "IC2") (pin "5") (pinfunction "+IN_5") (pintype "input"))
      (node (ref "IC3") (pin "3") (pinfunction "+IN_3") (pintype "input"))
      (node (ref "IC3") (pin "5") (pinfunction "+IN_5") (pintype "input"))
      (node (ref "IC5") (pin "3") (pinfunction "+IN_3") (pintype "input"))
      (node (ref "IC5") (pin "5") (pinfunction "+IN_5") (pintype "input"))
      (node (ref "IC6") (pin "3") (pinfunction "+IN_3") (pintype "input"))
      (node (ref "IC6") (pin "5") (pinfunction "+IN_5") (pintype "input"))
      (node (ref "IC7") (pin "3") (pinfunction "+IN_3") (pintype "input"))
      (node (ref "IC7") (pin "5") (pinfunction "+IN_5") (pintype "input"))
      (node (ref "IC8") (pin "3") (pinfunction "+IN_3") (pintype "input"))
      (node (ref "IC8") (pin "5") (pinfunction "+IN_5") (pintype "input"))
      (node (ref "IC9") (pin "3") (pinfunction "+IN_3") (pintype "input"))
      (node (ref "IC9") (pin "5") (pinfunction "+IN_5") (pintype "input"))
      (node (ref "ISP1") (pin "6") (pinfunction "GND_6") (pintype "power_in"))
      (node (ref "JP1") (pin "12") (pinfunction "12_12") (pintype "passive"))
      (node (ref "JP1") (pin "18") (pinfunction "18_18") (pintype "passive"))
      (node (ref "JP1") (pin "20") (pinfunction "20_20") (pintype "passive"))
      (node (ref "JP1") (pin "6") (pinfunction "6_6") (pintype "passive"))
      (node (ref "JP2") (pin "6") (pinfunction "6_6") (pintype "passive"))
      (node (ref "JP3") (pin "3") (pinfunction "3_3") (pintype "passive"))
      (node (ref "JP4") (pin "3") (pinfunction "3_3") (pintype "passive"))
      (node (ref "JP5") (pin "5") (pinfunction "5_5") (pintype "passive"))
      (node (ref "JP6") (pin "3") (pinfunction "3_3") (pintype "passive"))
      (node (ref "JP7") (pin "3") (pinfunction "3_3") (pintype "passive"))
      (node (ref "R28") (pin "1") (pinfunction "1_1") (pintype "passive"))
      (node (ref "R40") (pin "1") (pinfunction "1_1") (pintype "passive"))
      (node (ref "R49") (pin "1") (pinfunction "1_1") (pintype "passive"))
      (node (ref "R5") (pin "1") (pinfunction "1_1") (pintype "passive"))
      (node (ref "R50") (pin "1") (pinfunction "1_1") (pintype "passive"))
      (node (ref "R6") (pin "1") (pinfunction "1_1") (pintype "passive"))
      (node (ref "R64") (pin "1") (pinfunction "1_1") (pintype "passive"))
      (node (ref "R76") (pin "1") (pinfunction "1_1") (pintype "passive"))
      (node (ref "U1") (pin "3") (pinfunction "+IN_3") (pintype "input"))
      (node (ref "U1") (pin "4") (pinfunction "V-_4") (pintype "power_in"))
      (node (ref "U1") (pin "5") (pinfunction "+IN_5") (pintype "input"))
      (node (ref "U10") (pin "3") (pinfunction "+IN_3") (pintype "input"))
      (node (ref "U10") (pin "4") (pinfunction "V-_4") (pintype "power_in"))
      (node (ref "U10") (pin "5") (pinfunction "+IN_5") (pintype "input"))
      (node (ref "U11") (pin "12") (pinfunction "VSS_12") (pintype "bidirectional"))
      (node (ref "U11") (pin "8") (pinfunction "~{LDAC}_8") (pintype "bidirectional"))
      (node (ref "U12") (pin "12") (pinfunction "VSS_12") (pintype "bidirectional"))
      (node (ref "U12") (pin "8") (pinfunction "~{LDAC}_8") (pintype "bidirectional"))
      (node (ref "U13") (pin "21") (pinfunction "GND2_21") (pintype "power_in"))
      (node (ref "U13") (pin "3") (pinfunction "GND_3") (pintype "power_in"))
      (node (ref "U13") (pin "5") (pinfunction "GND1_5") (pintype "power_in"))
      (node (ref "U14") (pin "2") (pinfunction "ANODE_2") (pintype "passive"))
      (node (ref "U15") (pin "2") (pinfunction "ANODE_2") (pintype "passive"))
      (node (ref "U16") (pin "2") (pinfunction "ANODE_2") (pintype "passive"))
      (node (ref "U2") (pin "3") (pinfunction "+IN_3") (pintype "input"))
      (node (ref "U2") (pin "4") (pinfunction "V-_4") (pintype "power_in"))
      (node (ref "U2") (pin "5") (pinfunction "+IN_5") (pintype "input"))
      (node (ref "U3") (pin "3") (pinfunction "+IN_3") (pintype "input"))
      (node (ref "U3") (pin "4") (pinfunction "V-_4") (pintype "power_in"))
      (node (ref "U3") (pin "5") (pinfunction "+IN_5") (pintype "input"))
      (node (ref "U4") (pin "4") (pinfunction "V-_4") (pintype "power_in"))
      (node (ref "U5") (pin "12") (pinfunction "VSS_12") (pintype "bidirectional"))
      (node (ref "U5") (pin "8") (pinfunction "~{LDAC}_8") (pintype "bidirectional"))
      (node (ref "U6") (pin "12") (pinfunction "VSS_12") (pintype "bidirectional"))
      (node (ref "U6") (pin "8") (pinfunction "~{LDAC}_8") (pintype "bidirectional"))
      (node (ref "U7") (pin "3") (pinfunction "+IN_3") (pintype "input"))
      (node (ref "U7") (pin "4") (pinfunction "V-_4") (pintype "power_in"))
      (node (ref "U7") (pin "5") (pinfunction "+IN_5") (pintype "input"))
      (node (ref "U8") (pin "3") (pinfunction "+IN_3") (pintype "input"))
      (node (ref "U8") (pin "4") (pinfunction "V-_4") (pintype "power_in"))
      (node (ref "U8") (pin "5") (pinfunction "+IN_5") (pintype "input"))
      (node (ref "U9") (pin "4") (pinfunction "V-_4") (pintype "power_in"))
    )
    (net (code "39") (name "MISO") (class "Default")
      (node (ref "ISP1") (pin "1") (pinfunction "MISO_1") (pintype "input"))
      (node (ref "U13") (pin "16") (pinfunction "(PCINT4/MISO)PB4_16") (pintype "bidirectional"))
    )
    (net (code "40") (name "MOSI") (class "Default")
      (node (ref "ISP1") (pin "4") (pinfunction "MOSI_4") (pintype "output"))
      (node (ref "U11") (pin "5") (pinfunction "SDI_5") (pintype "bidirectional"))
      (node (ref "U12") (pin "5") (pinfunction "SDI_5") (pintype "bidirectional"))
      (node (ref "U13") (pin "15") (pinfunction "(PCINT3/OC2A/MOSI)PB3_15") (pintype "bidirectional"))
      (node (ref "U5") (pin "5") (pinfunction "SDI_5") (pintype "bidirectional"))
      (node (ref "U6") (pin "5") (pinfunction "SDI_5") (pintype "bidirectional"))
    )
    (net (code "41") (name "Net-(C33-+12V-PadPOS1)") (class "Default")
      (node (ref "C33") (pin "POS1") (pinfunction "+12V_POS1") (pintype "bidirectional"))
      (node (ref "C33") (pin "POS2") (pinfunction "+12V_POS2") (pintype "bidirectional"))
      (node (ref "D1") (pin "A") (pinfunction "A_A") (pintype "passive"))
    )
    (net (code "42") (name "Net-(C33--12V-PadNEG1)") (class "Default")
      (node (ref "C33") (pin "NEG1") (pinfunction "-12V_NEG1") (pintype "bidirectional"))
      (node (ref "C33") (pin "NEG2") (pinfunction "-12V_NEG2") (pintype "bidirectional"))
      (node (ref "D2") (pin "C") (pinfunction "C_C") (pintype "passive"))
    )
    (net (code "43") (name "Net-(IC1A--IN)") (class "Default")
      (node (ref "IC1") (pin "2") (pinfunction "-IN_2") (pintype "input"))
      (node (ref "R1") (pin "2") (pinfunction "2_2") (pintype "passive"))
      (node (ref "R7") (pin "1") (pinfunction "1_1") (pintype "passive"))
    )
    (net (code "44") (name "Net-(IC1A-OUT)") (class "Default")
      (node (ref "IC1") (pin "1") (pinfunction "OUT_1") (pintype "output"))
      (node (ref "R22") (pin "1") (pinfunction "1_1") (pintype "passive"))
      (node (ref "R7") (pin "2") (pinfunction "2_2") (pintype "passive"))
    )
    (net (code "45") (name "Net-(IC1B--IN)") (class "Default")
      (node (ref "IC1") (pin "6") (pinfunction "-IN_6") (pintype "input"))
      (node (ref "R3") (pin "2") (pinfunction "2_2") (pintype "passive"))
      (node (ref "R8") (pin "1") (pinfunction "1_1") (pintype "passive"))
    )
    (net (code "46") (name "Net-(IC1B-OUT)") (class "Default")
      (node (ref "IC1") (pin "7") (pinfunction "OUT_7") (pintype "output"))
      (node (ref "R24") (pin "1") (pinfunction "1_1") (pintype "passive"))
      (node (ref "R8") (pin "2") (pinfunction "2_2") (pintype "passive"))
    )
    (net (code "47") (name "Net-(IC2A--IN)") (class "Default")
      (node (ref "IC2") (pin "2") (pinfunction "-IN_2") (pintype "input"))
      (node (ref "R29") (pin "2") (pinfunction "2_2") (pintype "passive"))
      (node (ref "R30") (pin "2") (pinfunction "2_2") (pintype "passive"))
      (node (ref "R38") (pin "1") (pinfunction "1_1") (pintype "passive"))
    )
    (net (code "48") (name "Net-(IC2A-OUT)") (class "Default")
      (node (ref "IC2") (pin "1") (pinfunction "OUT_1") (pintype "output"))
      (node (ref "R38") (pin "2") (pinfunction "2_2") (pintype "passive"))
      (node (ref "R47") (pin "1") (pinfunction "1_1") (pintype "passive"))
    )
    (net (code "49") (name "Net-(IC2B--IN)") (class "Default")
      (node (ref "IC2") (pin "6") (pinfunction "-IN_6") (pintype "input"))
      (node (ref "R31") (pin "2") (pinfunction "2_2") (pintype "passive"))
      (node (ref "R32") (pin "2") (pinfunction "2_2") (pintype "passive"))
      (node (ref "R41") (pin "1") (pinfunction "1_1") (pintype "passive"))
    )
    (net (code "50") (name "Net-(IC2B-OUT)") (class "Default")
      (node (ref "IC2") (pin "7") (pinfunction "OUT_7") (pintype "output"))
      (node (ref "R41") (pin "2") (pinfunction "2_2") (pintype "passive"))
      (node (ref "R51") (pin "1") (pinfunction "1_1") (pintype "passive"))
    )
    (net (code "51") (name "Net-(IC3A--IN)") (class "Default")
      (node (ref "IC3") (pin "2") (pinfunction "-IN_2") (pintype "input"))
      (node (ref "R33") (pin "2") (pinfunction "2_2") (pintype "passive"))
      (node (ref "R34") (pin "2") (pinfunction "2_2") (pintype "passive"))
      (node (ref "R39") (pin "1") (pinfunction "1_1") (pintype "passive"))
    )
    (net (code "52") (name "Net-(IC3A-OUT)") (class "Default")
      (node (ref "IC3") (pin "1") (pinfunction "OUT_1") (pintype "output"))
      (node (ref "R39") (pin "2") (pinfunction "2_2") (pintype "passive"))
      (node (ref "R48") (pin "1") (pinfunction "1_1") (pintype "passive"))
    )
    (net (code "53") (name "Net-(IC3B--IN)") (class "Default")
      (node (ref "IC3") (pin "6") (pinfunction "-IN_6") (pintype "input"))
      (node (ref "R35") (pin "2") (pinfunction "2_2") (pintype "passive"))
      (node (ref "R36") (pin "2") (pinfunction "2_2") (pintype "passive"))
      (node (ref "R42") (pin "1") (pinfunction "1_1") (pintype "passive"))
    )
    (net (code "54") (name "Net-(IC3B-OUT)") (class "Default")
      (node (ref "IC3") (pin "7") (pinfunction "OUT_7") (pintype "output"))
      (node (ref "R42") (pin "2") (pinfunction "2_2") (pintype "passive"))
      (node (ref "R52") (pin "1") (pinfunction "1_1") (pintype "passive"))
    )
    (net (code "55") (name "Net-(IC4A--IN)") (class "Default")
      (node (ref "IC4") (pin "2") (pinfunction "-IN_2") (pintype "input"))
      (node (ref "R43") (pin "2") (pinfunction "2_2") (pintype "passive"))
      (node (ref "R53") (pin "1") (pinfunction "1_1") (pintype "passive"))
    )
    (net (code "56") (name "Net-(IC4A-OUT)") (class "Default")
      (node (ref "IC4") (pin "1") (pinfunction "OUT_1") (pintype "output"))
      (node (ref "R53") (pin "2") (pinfunction "2_2") (pintype "passive"))
      (node (ref "R70") (pin "1") (pinfunction "1_1") (pintype "passive"))
    )
    (net (code "57") (name "Net-(IC4B--IN)") (class "Default")
      (node (ref "IC4") (pin "6") (pinfunction "-IN_6") (pintype "input"))
      (node (ref "R45") (pin "2") (pinfunction "2_2") (pintype "passive"))
      (node (ref "R54") (pin "1") (pinfunction "1_1") (pintype "passive"))
    )
    (net (code "58") (name "Net-(IC4B-OUT)") (class "Default")
      (node (ref "IC4") (pin "7") (pinfunction "OUT_7") (pintype "output"))
      (node (ref "R54") (pin "2") (pinfunction "2_2") (pintype "passive"))
      (node (ref "R72") (pin "1") (pinfunction "1_1") (pintype "passive"))
    )
    (net (code "59") (name "Net-(IC5A--IN)") (class "Default")
      (node (ref "IC5") (pin "2") (pinfunction "-IN_2") (pintype "input"))
      (node (ref "R77") (pin "2") (pinfunction "2_2") (pintype "passive"))
      (node (ref "R78") (pin "2") (pinfunction "2_2") (pintype "passive"))
      (node (ref "R85") (pin "1") (pinfunction "1_1") (pintype "passive"))
    )
    (net (code "60") (name "Net-(IC5A-OUT)") (class "Default")
      (node (ref "IC5") (pin "1") (pinfunction "OUT_1") (pintype "output"))
      (node (ref "R85") (pin "2") (pinfunction "2_2") (pintype "passive"))
      (node (ref "R89") (pin "1") (pinfunction "1_1") (pintype "passive"))
    )
    (net (code "61") (name "Net-(IC5B--IN)") (class "Default")
      (node (ref "IC5") (pin "6") (pinfunction "-IN_6") (pintype "input"))
      (node (ref "R79") (pin "2") (pinfunction "2_2") (pintype "passive"))
      (node (ref "R80") (pin "2") (pinfunction "2_2") (pintype "passive"))
      (node (ref "R87") (pin "1") (pinfunction "1_1") (pintype "passive"))
    )
    (net (code "62") (name "Net-(IC5B-OUT)") (class "Default")
      (node (ref "IC5") (pin "7") (pinfunction "OUT_7") (pintype "output"))
      (node (ref "R87") (pin "2") (pinfunction "2_2") (pintype "passive"))
      (node (ref "R91") (pin "1") (pinfunction "1_1") (pintype "passive"))
    )
    (net (code "63") (name "Net-(IC6A--IN)") (class "Default")
      (node (ref "IC6") (pin "2") (pinfunction "-IN_2") (pintype "input"))
      (node (ref "R81") (pin "2") (pinfunction "2_2") (pintype "passive"))
      (node (ref "R82") (pin "2") (pinfunction "2_2") (pintype "passive"))
      (node (ref "R86") (pin "1") (pinfunction "1_1") (pintype "passive"))
    )
    (net (code "64") (name "Net-(IC6A-OUT)") (class "Default")
      (node (ref "IC6") (pin "1") (pinfunction "OUT_1") (pintype "output"))
      (node (ref "R86") (pin "2") (pinfunction "2_2") (pintype "passive"))
      (node (ref "R90") (pin "1") (pinfunction "1_1") (pintype "passive"))
    )
    (net (code "65") (name "Net-(IC6B--IN)") (class "Default")
      (node (ref "IC6") (pin "6") (pinfunction "-IN_6") (pintype "input"))
      (node (ref "R83") (pin "2") (pinfunction "2_2") (pintype "passive"))
      (node (ref "R84") (pin "2") (pinfunction "2_2") (pintype "passive"))
      (node (ref "R88") (pin "1") (pinfunction "1_1") (pintype "passive"))
    )
    (net (code "66") (name "Net-(IC6B-OUT)") (class "Default")
      (node (ref "IC6") (pin "7") (pinfunction "OUT_7") (pintype "output"))
      (node (ref "R88") (pin "2") (pinfunction "2_2") (pintype "passive"))
      (node (ref "R92") (pin "1") (pinfunction "1_1") (pintype "passive"))
    )
    (net (code "67") (name "Net-(IC8A--IN)") (class "Default")
      (node (ref "IC8") (pin "2") (pinfunction "-IN_2") (pintype "input"))
      (node (ref "R100") (pin "1") (pinfunction "1_1") (pintype "passive"))
      (node (ref "R98") (pin "1") (pinfunction "1_1") (pintype "passive"))
    )
    (net (code "68") (name "Net-(IC8B--IN)") (class "Default")
      (node (ref "IC8") (pin "6") (pinfunction "-IN_6") (pintype "input"))
      (node (ref "R102") (pin "2") (pinfunction "2_2") (pintype "passive"))
      (node (ref "R104") (pin "1") (pinfunction "1_1") (pintype "passive"))
    )
    (net (code "69") (name "Net-(IC9A--IN)") (class "Default")
      (node (ref "IC9") (pin "2") (pinfunction "-IN_2") (pintype "input"))
      (node (ref "R101") (pin "1") (pinfunction "1_1") (pintype "passive"))
      (node (ref "R99") (pin "1") (pinfunction "1_1") (pintype "passive"))
    )
    (net (code "70") (name "Net-(IC9B--IN)") (class "Default")
      (node (ref "IC9") (pin "6") (pinfunction "-IN_6") (pintype "input"))
      (node (ref "R103") (pin "2") (pinfunction "2_2") (pintype "passive"))
      (node (ref "R105") (pin "1") (pinfunction "1_1") (pintype "passive"))
    )
    (net (code "71") (name "Net-(U1A--IN)") (class "Default")
      (node (ref "R10") (pin "2") (pinfunction "2_2") (pintype "passive"))
      (node (ref "R17") (pin "1") (pinfunction "1_1") (pintype "passive"))
      (node (ref "R9") (pin "2") (pinfunction "2_2") (pintype "passive"))
      (node (ref "U1") (pin "2") (pinfunction "-IN_2") (pintype "input"))
    )
    (net (code "72") (name "Net-(U1A-OUT)") (class "Default")
      (node (ref "R17") (pin "2") (pinfunction "2_2") (pintype "passive"))
      (node (ref "U1") (pin "1") (pinfunction "OUT_1") (pintype "output"))
      (node (ref "U5") (pin "13") (pinfunction "VREFA_13") (pintype "bidirectional"))
    )
    (net (code "73") (name "Net-(U1B--IN)") (class "Default")
      (node (ref "R11") (pin "2") (pinfunction "2_2") (pintype "passive"))
      (node (ref "R12") (pin "2") (pinfunction "2_2") (pintype "passive"))
      (node (ref "R18") (pin "1") (pinfunction "1_1") (pintype "passive"))
      (node (ref "U1") (pin "6") (pinfunction "-IN_6") (pintype "input"))
    )
    (net (code "74") (name "Net-(U1B-OUT)") (class "Default")
      (node (ref "R18") (pin "2") (pinfunction "2_2") (pintype "passive"))
      (node (ref "U1") (pin "7") (pinfunction "OUT_7") (pintype "output"))
      (node (ref "U5") (pin "11") (pinfunction "VREFB_11") (pintype "bidirectional"))
    )
    (net (code "75") (name "Net-(U2A--IN)") (class "Default")
      (node (ref "R13") (pin "2") (pinfunction "2_2") (pintype "passive"))
      (node (ref "R14") (pin "2") (pinfunction "2_2") (pintype "passive"))
      (node (ref "R19") (pin "1") (pinfunction "1_1") (pintype "passive"))
      (node (ref "U2") (pin "2") (pinfunction "-IN_2") (pintype "input"))
    )
    (net (code "76") (name "Net-(U2A-OUT)") (class "Default")
      (node (ref "R19") (pin "2") (pinfunction "2_2") (pintype "passive"))
      (node (ref "U2") (pin "1") (pinfunction "OUT_1") (pintype "output"))
      (node (ref "U6") (pin "13") (pinfunction "VREFA_13") (pintype "bidirectional"))
    )
    (net (code "77") (name "Net-(U2B--IN)") (class "Default")
      (node (ref "R15") (pin "2") (pinfunction "2_2") (pintype "passive"))
      (node (ref "R16") (pin "2") (pinfunction "2_2") (pintype "passive"))
      (node (ref "R20") (pin "1") (pinfunction "1_1") (pintype "passive"))
      (node (ref "U2") (pin "6") (pinfunction "-IN_6") (pintype "input"))
    )
    (net (code "78") (name "Net-(U2B-OUT)") (class "Default")
      (node (ref "R20") (pin "2") (pinfunction "2_2") (pintype "passive"))
      (node (ref "U2") (pin "7") (pinfunction "OUT_7") (pintype "output"))
      (node (ref "U6") (pin "11") (pinfunction "VREFB_11") (pintype "bidirectional"))
    )
    (net (code "79") (name "Net-(U3A--IN)") (class "Default")
      (node (ref "C39") (pin "1") (pinfunction "1_1") (pintype "passive"))
      (node (ref "R21") (pin "2") (pinfunction "2_2") (pintype "passive"))
      (node (ref "R22") (pin "2") (pinfunction "2_2") (pintype "passive"))
      (node (ref "R26") (pin "1") (pinfunction "1_1") (pintype "passive"))
      (node (ref "U3") (pin "2") (pinfunction "-IN_2") (pintype "input"))
    )
    (net (code "80") (name "Net-(U3B--IN)") (class "Default")
      (node (ref "C40") (pin "1") (pinfunction "1_1") (pintype "passive"))
      (node (ref "R23") (pin "2") (pinfunction "2_2") (pintype "passive"))
      (node (ref "R24") (pin "2") (pinfunction "2_2") (pintype "passive"))
      (node (ref "R27") (pin "1") (pinfunction "1_1") (pintype "passive"))
      (node (ref "U3") (pin "6") (pinfunction "-IN_6") (pintype "input"))
    )
    (net (code "81") (name "Net-(U4A-+IN)") (class "Default")
      (node (ref "R25") (pin "1") (pinfunction "1_1") (pintype "passive"))
      (node (ref "R28") (pin "2") (pinfunction "2_2") (pintype "passive"))
      (node (ref "U4") (pin "3") (pinfunction "+IN_3") (pintype "input"))
    )
    (net (code "82") (name "Net-(U4B-+IN)") (class "Default")
      (node (ref "R37") (pin "1") (pinfunction "1_1") (pintype "passive"))
      (node (ref "R40") (pin "2") (pinfunction "2_2") (pintype "passive"))
      (node (ref "U4") (pin "5") (pinfunction "+IN_5") (pintype "input"))
    )
    (net (code "83") (name "Net-(U5-VOUT_A)") (class "Default")
      (node (ref "R30") (pin "1") (pinfunction "1_1") (pintype "passive"))
      (node (ref "U5") (pin "14") (pinfunction "VOUT_A_14") (pintype "bidirectional"))
    )
    (net (code "84") (name "Net-(U5-VOUT_B)") (class "Default")
      (node (ref "R31") (pin "1") (pinfunction "1_1") (pintype "passive"))
      (node (ref "U5") (pin "10") (pinfunction "VOUT_B_10") (pintype "bidirectional"))
    )
    (net (code "85") (name "Net-(U6-VOUT_A)") (class "Default")
      (node (ref "R34") (pin "1") (pinfunction "1_1") (pintype "passive"))
      (node (ref "U6") (pin "14") (pinfunction "VOUT_A_14") (pintype "bidirectional"))
    )
    (net (code "86") (name "Net-(U6-VOUT_B)") (class "Default")
      (node (ref "R35") (pin "1") (pinfunction "1_1") (pintype "passive"))
      (node (ref "U6") (pin "10") (pinfunction "VOUT_B_10") (pintype "bidirectional"))
    )
    (net (code "87") (name "Net-(U7A--IN)") (class "Default")
      (node (ref "R55") (pin "2") (pinfunction "2_2") (pintype "passive"))
      (node (ref "R56") (pin "2") (pinfunction "2_2") (pintype "passive"))
      (node (ref "R65") (pin "1") (pinfunction "1_1") (pintype "passive"))
      (node (ref "U7") (pin "2") (pinfunction "-IN_2") (pintype "input"))
    )
    (net (code "88") (name "Net-(U7B--IN)") (class "Default")
      (node (ref "R57") (pin "2") (pinfunction "2_2") (pintype "passive"))
      (node (ref "R58") (pin "2") (pinfunction "2_2") (pintype "passive"))
      (node (ref "R66") (pin "1") (pinfunction "1_1") (pintype "passive"))
      (node (ref "U7") (pin "6") (pinfunction "-IN_6") (pintype "input"))
    )
    (net (code "89") (name "Net-(U8A--IN)") (class "Default")
      (node (ref "R59") (pin "2") (pinfunction "2_2") (pintype "passive"))
      (node (ref "R60") (pin "2") (pinfunction "2_2") (pintype "passive"))
      (node (ref "R67") (pin "1") (pinfunction "1_1") (pintype "passive"))
      (node (ref "U8") (pin "2") (pinfunction "-IN_2") (pintype "input"))
    )
    (net (code "90") (name "Net-(U8B--IN)") (class "Default")
      (node (ref "R61") (pin "2") (pinfunction "2_2") (pintype "passive"))
      (node (ref "R62") (pin "2") (pinfunction "2_2") (pintype "passive"))
      (node (ref "R68") (pin "1") (pinfunction "1_1") (pintype "passive"))
      (node (ref "U8") (pin "6") (pinfunction "-IN_6") (pintype "input"))
    )
    (net (code "91") (name "Net-(U9A-+IN)") (class "Default")
      (node (ref "R63") (pin "1") (pinfunction "1_1") (pintype "passive"))
      (node (ref "R64") (pin "2") (pinfunction "2_2") (pintype "passive"))
      (node (ref "U9") (pin "3") (pinfunction "+IN_3") (pintype "input"))
    )
    (net (code "92") (name "Net-(U9B-+IN)") (class "Default")
      (node (ref "R75") (pin "1") (pinfunction "1_1") (pintype "passive"))
      (node (ref "R76") (pin "2") (pinfunction "2_2") (pintype "passive"))
      (node (ref "U9") (pin "5") (pinfunction "+IN_5") (pintype "input"))
    )
    (net (code "93") (name "Net-(U10A--IN)") (class "Default")
      (node (ref "C41") (pin "1") (pinfunction "1_1") (pintype "passive"))
      (node (ref "R69") (pin "2") (pinfunction "2_2") (pintype "passive"))
      (node (ref "R70") (pin "2") (pinfunction "2_2") (pintype "passive"))
      (node (ref "R73") (pin "1") (pinfunction "1_1") (pintype "passive"))
      (node (ref "U10") (pin "2") (pinfunction "-IN_2") (pintype "input"))
    )
    (net (code "94") (name "Net-(U10B--IN)") (class "Default")
      (node (ref "C42") (pin "1") (pinfunction "1_1") (pintype "passive"))
      (node (ref "R71") (pin "2") (pinfunction "2_2") (pintype "passive"))
      (node (ref "R72") (pin "2") (pinfunction "2_2") (pintype "passive"))
      (node (ref "R74") (pin "1") (pinfunction "1_1") (pintype "passive"))
      (node (ref "U10") (pin "6") (pinfunction "-IN_6") (pintype "input"))
    )
    (net (code "95") (name "Net-(U11-VOUT_A)") (class "Default")
      (node (ref "R78") (pin "1") (pinfunction "1_1") (pintype "passive"))
      (node (ref "U11") (pin "14") (pinfunction "VOUT_A_14") (pintype "bidirectional"))
    )
    (net (code "96") (name "Net-(U11-VOUT_B)") (class "Default")
      (node (ref "R79") (pin "1") (pinfunction "1_1") (pintype "passive"))
      (node (ref "U11") (pin "10") (pinfunction "VOUT_B_10") (pintype "bidirectional"))
    )
    (net (code "97") (name "Net-(U11-VREFA)") (class "Default")
      (node (ref "R65") (pin "2") (pinfunction "2_2") (pintype "passive"))
      (node (ref "U11") (pin "13") (pinfunction "VREFA_13") (pintype "bidirectional"))
      (node (ref "U7") (pin "1") (pinfunction "OUT_1") (pintype "output"))
    )
    (net (code "98") (name "Net-(U11-VREFB)") (class "Default")
      (node (ref "R66") (pin "2") (pinfunction "2_2") (pintype "passive"))
      (node (ref "U11") (pin "11") (pinfunction "VREFB_11") (pintype "bidirectional"))
      (node (ref "U7") (pin "7") (pinfunction "OUT_7") (pintype "output"))
    )
    (net (code "99") (name "Net-(U12-VOUT_A)") (class "Default")
      (node (ref "R82") (pin "1") (pinfunction "1_1") (pintype "passive"))
      (node (ref "U12") (pin "14") (pinfunction "VOUT_A_14") (pintype "bidirectional"))
    )
    (net (code "100") (name "Net-(U12-VOUT_B)") (class "Default")
      (node (ref "R83") (pin "1") (pinfunction "1_1") (pintype "passive"))
      (node (ref "U12") (pin "10") (pinfunction "VOUT_B_10") (pintype "bidirectional"))
    )
    (net (code "101") (name "Net-(U12-VREFA)") (class "Default")
      (node (ref "R67") (pin "2") (pinfunction "2_2") (pintype "passive"))
      (node (ref "U12") (pin "13") (pinfunction "VREFA_13") (pintype "bidirectional"))
      (node (ref "U8") (pin "1") (pinfunction "OUT_1") (pintype "output"))
    )
    (net (code "102") (name "Net-(U12-VREFB)") (class "Default")
      (node (ref "R68") (pin "2") (pinfunction "2_2") (pintype "passive"))
      (node (ref "U12") (pin "11") (pinfunction "VREFB_11") (pintype "bidirectional"))
      (node (ref "U8") (pin "7") (pinfunction "OUT_7") (pintype "output"))
    )
    (net (code "103") (name "Net-(U13-(PCINT6{slash}XTAL1{slash}TOSC1)PB6)") (class "Default")
      (node (ref "C26") (pin "1") (pinfunction "1_1") (pintype "passive"))
      (node (ref "Q1") (pin "1") (pinfunction "1_1") (pintype "passive"))
      (node (ref "U13") (pin "7") (pinfunction "(PCINT6/XTAL1/TOSC1)PB6_7") (pintype "bidirectional"))
    )
    (net (code "104") (name "Net-(U13-(PCINT7{slash}XTAL2{slash}TOSC2)PB7)") (class "Default")
      (node (ref "C25") (pin "1") (pinfunction "1_1") (pintype "passive"))
      (node (ref "Q1") (pin "2") (pinfunction "2_2") (pintype "passive"))
      (node (ref "U13") (pin "8") (pinfunction "(PCINT7/XTAL2/TOSC2)PB7_8") (pintype "bidirectional"))
    )
    (net (code "105") (name "Net-(U13-AREF)") (class "Default")
      (node (ref "C24") (pin "1") (pinfunction "1_1") (pintype "passive"))
      (node (ref "U13") (pin "20") (pinfunction "AREF_20") (pintype "power_in"))
    )
    (net (code "106") (name "OUT_L") (class "Default")
      (node (ref "JP5") (pin "1") (pinfunction "1_1") (pintype "passive"))
      (node (ref "R98") (pin "2") (pinfunction "2_2") (pintype "passive"))
    )
    (net (code "107") (name "OUT_R") (class "Default")
      (node (ref "JP5") (pin "2") (pinfunction "2_2") (pintype "passive"))
      (node (ref "R99") (pin "2") (pinfunction "2_2") (pintype "passive"))
    )
    (net (code "108") (name "PAN_CV_1") (class "Default")
      (node (ref "C39") (pin "2") (pinfunction "2_2") (pintype "passive"))
      (node (ref "R26") (pin "2") (pinfunction "2_2") (pintype "passive"))
      (node (ref "U13") (pin "27") (pinfunction "(ADC4/SDA/PCINT12)PC4_27") (pintype "bidirectional"))
      (node (ref "U3") (pin "1") (pinfunction "OUT_1") (pintype "output"))
    )
    (net (code "109") (name "PAN_CV_2") (class "Default")
      (node (ref "C40") (pin "2") (pinfunction "2_2") (pintype "passive"))
      (node (ref "R27") (pin "2") (pinfunction "2_2") (pintype "passive"))
      (node (ref "U13") (pin "28") (pinfunction "(ADC5/SCL/PCINT13)PC5_28") (pintype "bidirectional"))
      (node (ref "U3") (pin "7") (pinfunction "OUT_7") (pintype "output"))
    )
    (net (code "110") (name "PAN_CV_3") (class "Default")
      (node (ref "C41") (pin "2") (pinfunction "2_2") (pintype "passive"))
      (node (ref "R73") (pin "2") (pinfunction "2_2") (pintype "passive"))
      (node (ref "U10") (pin "1") (pinfunction "OUT_1") (pintype "output"))
      (node (ref "U13") (pin "19") (pinfunction "ADC6_19") (pintype "input"))
    )
    (net (code "111") (name "PAN_CV_4") (class "Default")
      (node (ref "C42") (pin "2") (pinfunction "2_2") (pintype "passive"))
      (node (ref "R74") (pin "2") (pinfunction "2_2") (pintype "passive"))
      (node (ref "U10") (pin "7") (pinfunction "OUT_7") (pintype "output"))
      (node (ref "U13") (pin "22") (pinfunction "ADC7_22") (pintype "input"))
    )
    (net (code "112") (name "REF_5") (class "Default")
      (node (ref "C36") (pin "1") (pinfunction "1_1") (pintype "passive"))
      (node (ref "JP2") (pin "8") (pinfunction "8_8") (pintype "passive"))
      (node (ref "R106") (pin "1") (pinfunction "1_1") (pintype "passive"))
      (node (ref "U14") (pin "1") (pinfunction "CATHODE_1") (pintype "passive"))
    )
    (net (code "113") (name "REF_10") (class "Default")
      (node (ref "C37") (pin "1") (pinfunction "1_1") (pintype "passive"))
      (node (ref "JP2") (pin "9") (pinfunction "9_9") (pintype "passive"))
      (node (ref "R107") (pin "1") (pinfunction "1_1") (pintype "passive"))
      (node (ref "U15") (pin "1") (pinfunction "CATHODE_1") (pintype "passive"))
    )
    (net (code "114") (name "RESET") (class "Default")
      (node (ref "ISP1") (pin "5") (pinfunction "RST_5") (pintype "output"))
      (node (ref "R93") (pin "1") (pinfunction "1_1") (pintype "passive"))
      (node (ref "U13") (pin "29") (pinfunction "(RESET/PCINT14)PC6_29") (pintype "bidirectional"))
    )
    (net (code "115") (name "SCK") (class "Default")
      (node (ref "ISP1") (pin "3") (pinfunction "SCK_3") (pintype "output"))
      (node (ref "U11") (pin "4") (pinfunction "SCK_4") (pintype "bidirectional"))
      (node (ref "U12") (pin "4") (pinfunction "SCK_4") (pintype "bidirectional"))
      (node (ref "U13") (pin "17") (pinfunction "(SCK/PCINT5)PB5_17") (pintype "bidirectional"))
      (node (ref "U5") (pin "4") (pinfunction "SCK_4") (pintype "bidirectional"))
      (node (ref "U6") (pin "4") (pinfunction "SCK_4") (pintype "bidirectional"))
    )
    (net (code "116") (name "SUM_L") (class "Default")
      (node (ref "C43") (pin "1") (pinfunction "1_1") (pintype "passive"))
      (node (ref "IC7") (pin "2") (pinfunction "-IN_2") (pintype "input"))
      (node (ref "R47") (pin "2") (pinfunction "2_2") (pintype "passive"))
      (node (ref "R48") (pin "2") (pinfunction "2_2") (pintype "passive"))
      (node (ref "R89") (pin "2") (pinfunction "2_2") (pintype "passive"))
      (node (ref "R90") (pin "2") (pinfunction "2_2") (pintype "passive"))
      (node (ref "R94") (pin "2") (pinfunction "2_2") (pintype "passive"))
      (node (ref "R96") (pin "1") (pinfunction "1_1") (pintype "passive"))
    )
    (net (code "117") (name "SUM_R") (class "Default")
      (node (ref "C44") (pin "1") (pinfunction "1_1") (pintype "passive"))
      (node (ref "IC7") (pin "6") (pinfunction "-IN_6") (pintype "input"))
      (node (ref "R51") (pin "2") (pinfunction "2_2") (pintype "passive"))
      (node (ref "R52") (pin "2") (pinfunction "2_2") (pintype "passive"))
      (node (ref "R91") (pin "2") (pinfunction "2_2") (pintype "passive"))
      (node (ref "R92") (pin "2") (pinfunction "2_2") (pintype "passive"))
      (node (ref "R95") (pin "2") (pinfunction "2_2") (pintype "passive"))
      (node (ref "R97") (pin "1") (pinfunction "1_1") (pintype "passive"))
    )
    (net (code "118") (name "VOL_CV_1") (class "Default")
      (node (ref "U13") (pin "23") (pinfunction "(ADC0/PCINT8)PC0_23") (pintype "bidirectional"))
      (node (ref "U4") (pin "1") (pinfunction "OUT_1") (pintype "output"))
      (node (ref "U4") (pin "2") (pinfunction "-IN_2") (pintype "input"))
    )
    (net (code "119") (name "VOL_CV_2") (class "Default")
      (node (ref "U13") (pin "24") (pinfunction "(ADC1/PCINT9)PC1_24") (pintype "bidirectional"))
      (node (ref "U4") (pin "6") (pinfunction "-IN_6") (pintype "input"))
      (node (ref "U4") (pin "7") (pinfunction "OUT_7") (pintype "output"))
    )
    (net (code "120") (name "VOL_CV_3") (class "Default")
      (node (ref "U13") (pin "25") (pinfunction "(ADC2/PCINT10)PC2_25") (pintype "bidirectional"))
      (node (ref "U9") (pin "1") (pinfunction "OUT_1") (pintype "output"))
      (node (ref "U9") (pin "2") (pinfunction "-IN_2") (pintype "input"))
    )
    (net (code "121") (name "VOL_CV_4") (class "Default")
      (node (ref "U13") (pin "26") (pinfunction "(ADC3/PCINT11)PC3_26") (pintype "bidirectional"))
      (node (ref "U9") (pin "6") (pinfunction "-IN_6") (pintype "input"))
      (node (ref "U9") (pin "7") (pinfunction "OUT_7") (pintype "output"))
    )
    (net (code "122") (name "unconnected-(U13-(PCINT0{slash}CLKO{slash}ICP1)PB0-Pad12)") (class "Default")
      (node (ref "U13") (pin "12") (pinfunction "(PCINT0/CLKO/ICP1)PB0_12") (pintype "bidirectional"))
    )
    (net (code "123") (name "unconnected-(U13-(PCINT1{slash}OC1A)PB1-Pad13)") (class "Default")
      (node (ref "U13") (pin "13") (pinfunction "(PCINT1/OC1A)PB1_13") (pintype "bidirectional"))
    )
    (net (code "124") (name "unconnected-(U13-(PCINT2{slash}SS{slash}OC1B)PB2-Pad14)") (class "Default")
      (node (ref "U13") (pin "14") (pinfunction "(PCINT2/SS/OC1B)PB2_14") (pintype "bidirectional"))
    )
    (net (code "125") (name "unconnected-(U13-PD4(PCINT20{slash}XCK{slash}T0)-Pad2)") (class "Default")
      (node (ref "U13") (pin "2") (pinfunction "PD4(PCINT20/XCK/T0)_2") (pintype "bidirectional"))
    )
    (net (code "126") (name "unconnected-(U13-PD5(PCINT21{slash}OC0B{slash}T1)-Pad9)") (class "Default")
      (node (ref "U13") (pin "9") (pinfunction "PD5(PCINT21/OC0B/T1)_9") (pintype "bidirectional"))
    )
    (net (code "127") (name "unconnected-(U13-PD6(PCINT22{slash}OC0A{slash}AIN0)-Pad10)") (class "Default")
      (node (ref "U13") (pin "10") (pinfunction "PD6(PCINT22/OC0A/AIN0)_10") (pintype "bidirectional"))
    )
    (net (code "128") (name "unconnected-(U13-PD7(PCINT23{slash}AIN1)-Pad11)") (class "Default")
      (node (ref "U13") (pin "11") (pinfunction "PD7(PCINT23/AIN1)_11") (pintype "bidirectional"))
    )
    (net (code "129") (name "unconnected-(U14-NC-Pad3)") (class "Default")
      (node (ref "U14") (pin "3") (pinfunction "NC_3") (pintype "passive"))
    )
    (net (code "130") (name "unconnected-(U15-NC-Pad3)") (class "Default")
      (node (ref "U15") (pin "3") (pinfunction "NC_3") (pintype "passive"))
    )
    (net (code "131") (name "unconnected-(U16-NC-Pad3)") (class "Default")
      (node (ref "U16") (pin "3") (pinfunction "NC_3") (pintype "passive"))
    )
  )
)
